# OBCv4_1.net
KiCad netlist of a schematic drawn in EAGLE
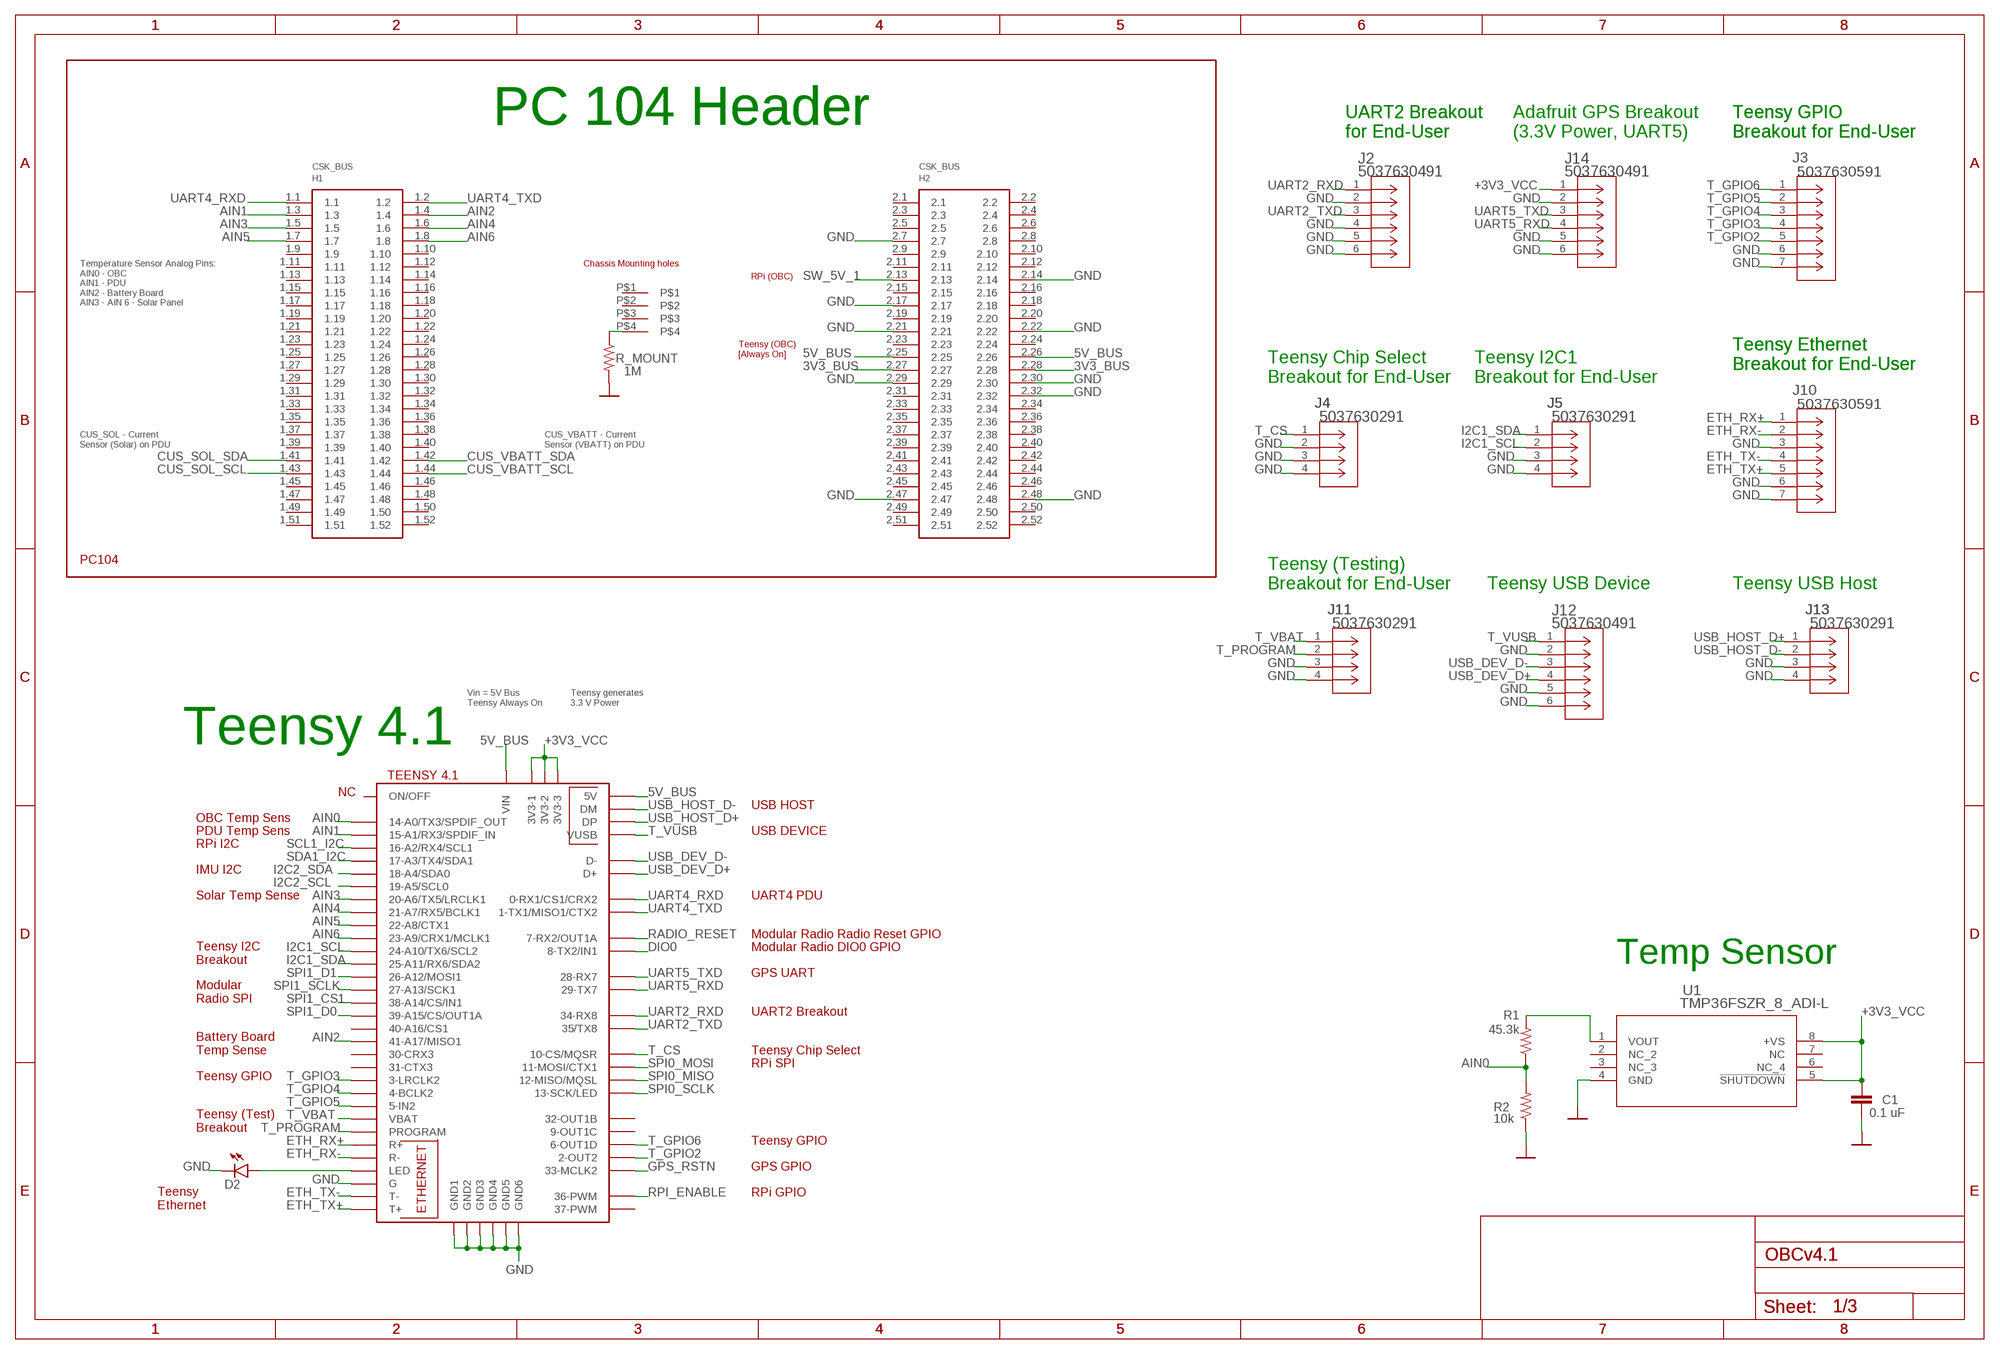
[diagram p0: schematic, sheet 1]
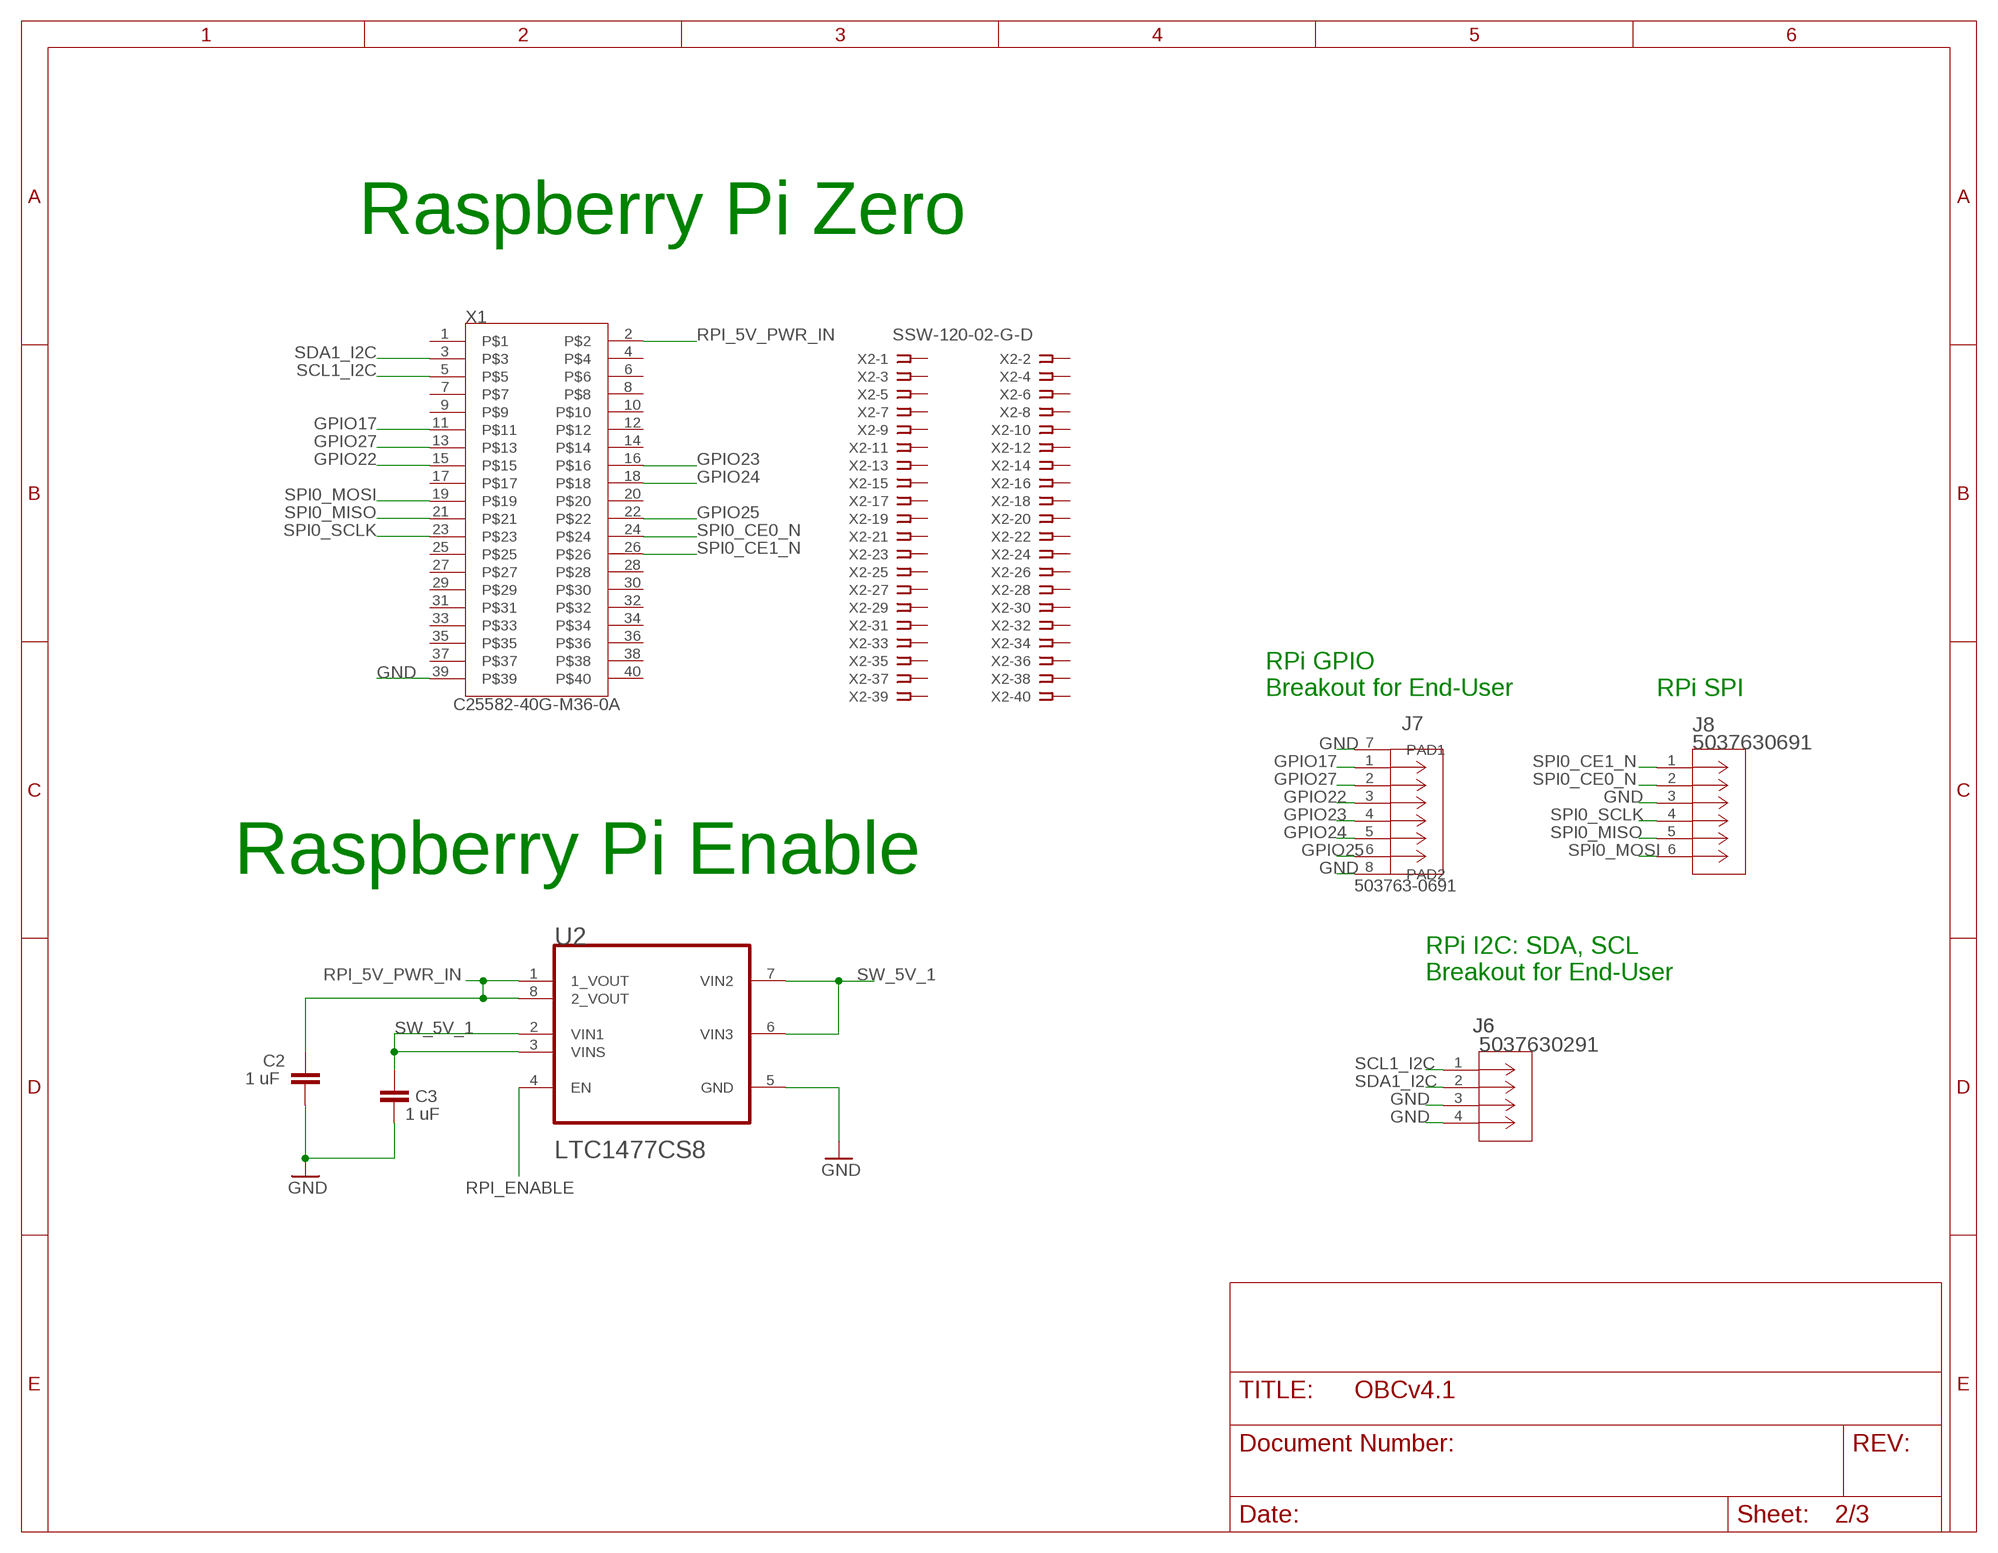
[diagram p1: schematic, sheet 2]
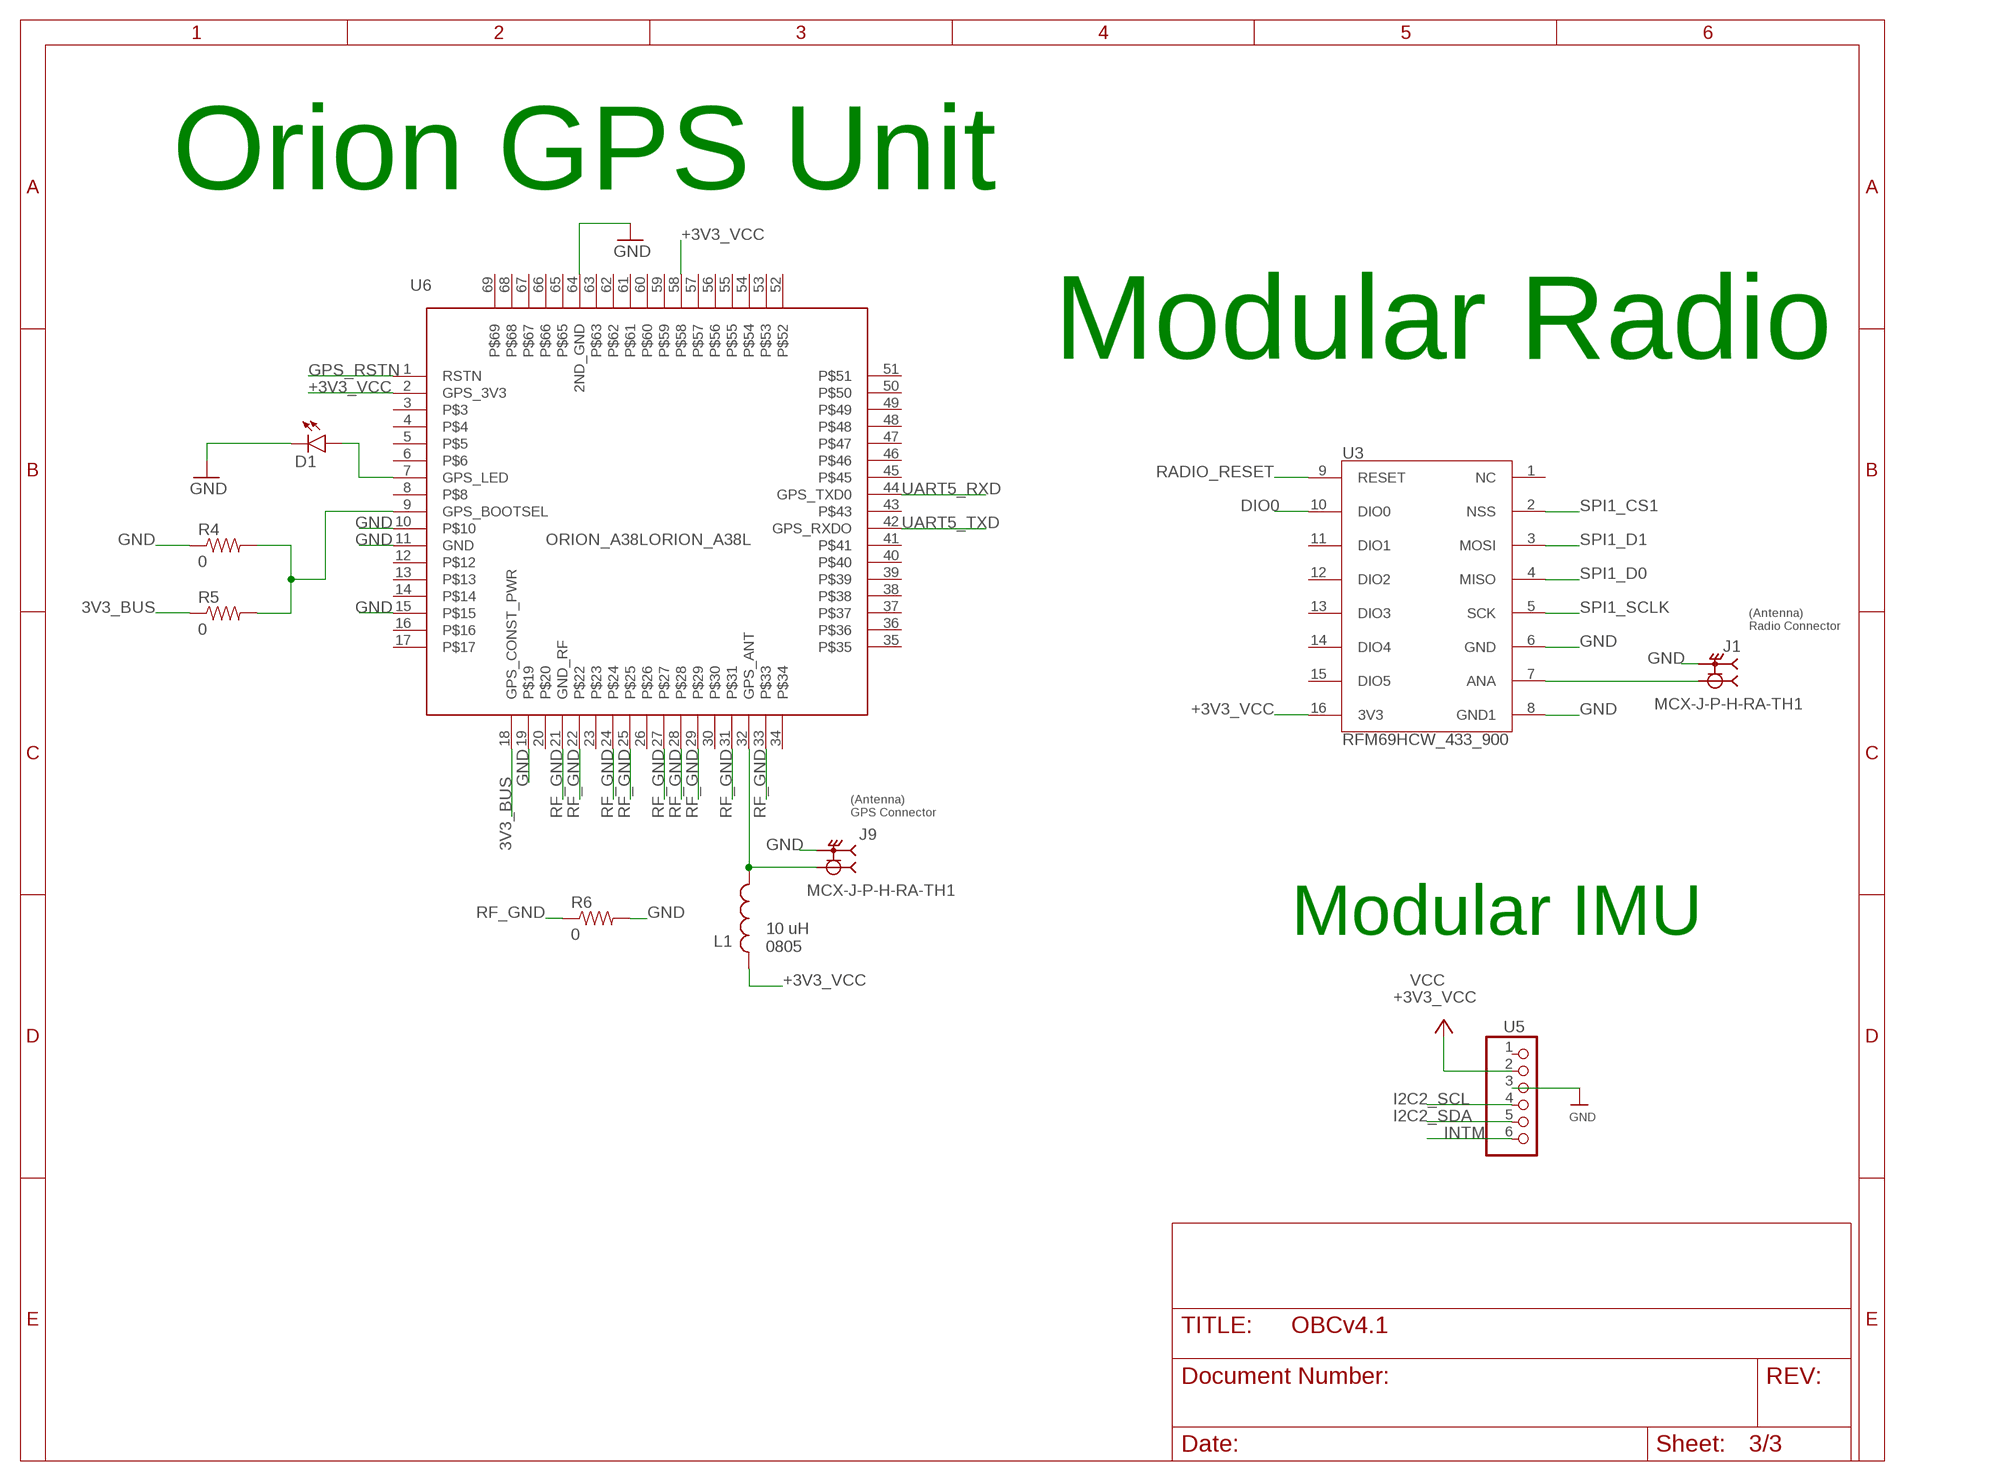
[diagram p2: schematic, sheet 3]

(export (version "E")
  (design (tool "Eeschema 10.0.6"))
  (components
    (comp (ref "C1")
      (value "0.1 uF")
      (footprint "eagle-import:0805")
      (libsource (lib "eagle-import") (part "CAP0805"))
    )
    (comp (ref "D2")
      (value "LEDCHIP-LED0603")
      (footprint "eagle-import:CHIP-LED0603")
      (libsource (lib "eagle-import") (part "LEDCHIP-LED0603"))
    )
    (comp (ref "H1")
      (value "PC104_WCONN")
      (footprint "eagle-import:PC104_WCONN")
      (libsource (lib "eagle-import") (part "PC104_WCONN"))
    )
    (comp (ref "J2")
      (value "5037630491")
      (footprint "eagle-import:CON_5037630491")
      (fields (field (name "COPYRIGHT") "Copyright (C) 2018 Accelerated Designs. All rights reserved"))
      (libsource (lib "eagle-import") (part "5037630491"))
    )
    (comp (ref "J3")
      (value "5037630591")
      (footprint "eagle-import:CON_5037630591")
      (fields (field (name "COPYRIGHT") "Copyright (C) 2021 Ultra Librarian. All rights reserved."))
      (libsource (lib "eagle-import") (part "5037630591"))
    )
    (comp (ref "J4")
      (value "5037630291")
      (footprint "eagle-import:CON_5037630291")
      (fields (field (name "COPYRIGHT") "Copyright (C) 2018 Accelerated Designs. All rights reserved"))
      (libsource (lib "eagle-import") (part "5037630291"))
    )
    (comp (ref "J5")
      (value "5037630291")
      (footprint "eagle-import:CON_5037630291")
      (fields (field (name "COPYRIGHT") "Copyright (C) 2018 Accelerated Designs. All rights reserved"))
      (libsource (lib "eagle-import") (part "5037630291"))
    )
    (comp (ref "J10")
      (value "5037630591")
      (footprint "eagle-import:CON_5037630591")
      (fields (field (name "COPYRIGHT") "Copyright (C) 2021 Ultra Librarian. All rights reserved."))
      (libsource (lib "eagle-import") (part "5037630591"))
    )
    (comp (ref "J11")
      (value "5037630291")
      (footprint "eagle-import:CON_5037630291")
      (fields (field (name "COPYRIGHT") "Copyright (C) 2018 Accelerated Designs. All rights reserved"))
      (libsource (lib "eagle-import") (part "5037630291"))
    )
    (comp (ref "J12")
      (value "5037630491")
      (footprint "eagle-import:CON_5037630491")
      (fields (field (name "COPYRIGHT") "Copyright (C) 2018 Accelerated Designs. All rights reserved"))
      (libsource (lib "eagle-import") (part "5037630491"))
    )
    (comp (ref "J13")
      (value "5037630291")
      (footprint "eagle-import:CON_5037630291")
      (fields (field (name "COPYRIGHT") "Copyright (C) 2018 Accelerated Designs. All rights reserved"))
      (libsource (lib "eagle-import") (part "5037630291"))
    )
    (comp (ref "J14")
      (value "5037630491")
      (footprint "eagle-import:CON_5037630491")
      (fields (field (name "COPYRIGHT") "Copyright (C) 2018 Accelerated Designs. All rights reserved"))
      (libsource (lib "eagle-import") (part "5037630491"))
    )
    (comp (ref "R1")
      (value "45.3k")
      (footprint "eagle-import:0805")
      (libsource (lib "eagle-import") (part "RESISTOR0805-RES"))
    )
    (comp (ref "R2")
      (value "10k")
      (footprint "eagle-import:0805")
      (libsource (lib "eagle-import") (part "RESISTOR0805-RES"))
    )
    (comp (ref "R_MOUNT")
      (value "1M")
      (footprint "eagle-import:0805")
      (libsource (lib "eagle-import") (part "RESISTOR0805-RES"))
    )
    (comp (ref "U$1")
      (value "TEENSY41")
      (footprint "eagle-import:TEENSY41")
      (libsource (lib "eagle-import") (part "TEENSY41"))
    )
    (comp (ref "U1")
      (value "TMP36FSZR_8_ADI-L")
      (footprint "eagle-import:R_8_ADI-L")
      (fields
        (field (name "MANUFACTURER_PART_NUMBER") "TMP36FSZ")
        (field (name "COPYRIGHT") "Copyright (C) 2021 Ultra Librarian. All rights reserved.")
      )
      (libsource (lib "eagle-import") (part "TMP36FSZR_8_ADI-L"))
    )
    (comp (ref "C2")
      (value "1 uF")
      (footprint "eagle-import:0805")
      (libsource (lib "eagle-import") (part "CAP0805"))
    )
    (comp (ref "C3")
      (value "1 uF")
      (footprint "eagle-import:0805")
      (libsource (lib "eagle-import") (part "CAP0805"))
    )
    (comp (ref "J6")
      (value "5037630291")
      (footprint "eagle-import:CON_5037630291")
      (fields (field (name "COPYRIGHT") "Copyright (C) 2018 Accelerated Designs. All rights reserved"))
      (libsource (lib "eagle-import") (part "5037630291"))
    )
    (comp (ref "J7")
      (value "503763-0691")
      (footprint "eagle-import:CONN_503763-0691_MOL")
      (fields (field (name "COPYRIGHT") "Copyright (C) 2018 Accelerated Designs. All rights reserved"))
      (libsource (lib "eagle-import") (part "503763-0691"))
    )
    (comp (ref "J8")
      (value "5037630691")
      (footprint "eagle-import:CONN_503763-0691_MOL")
      (fields
        (field (name "MANUFACTURER_PART_NUMBER") "503763-0691")
        (field (name "COPYRIGHT") "Copyright (C) 2018 Accelerated Designs. All rights reserved")
      )
      (libsource (lib "eagle-import") (part "5037630691"))
    )
    (comp (ref "U2")
      (value "LTC1477CS8LINEAR_TECHNOLOGY_LTC1477CS8_0_2")
      (footprint "eagle-import:LINEAR_TECHNOLOGY_LTC1477CS8_2")
      (fields (field (name "MF") "Linear Technology") (field (name "MPN") "LTC1477CS8"))
      (libsource (lib "eagle-import") (part "LTC1477CS8LINEAR_TECHNOLOGY_LTC1477CS8_0_2"))
    )
    (comp (ref "X1")
      (value "C25582-40G-M36-0A")
      (footprint "eagle-import:ADAFRUIT_C25582-40G-M36-0A_0")
      (libsource (lib "eagle-import") (part "C25582-40G-M36-0A"))
    )
    (comp (ref "X2")
      (value "SSW-120-02-G-D")
      (footprint "eagle-import:SSW-120-02-G-D")
      (fields (field (name "MF") "Samtec Inc."))
      (libsource (lib "eagle-import") (part "SSW-120-02-G-D"))
    )
    (comp (ref "D1")
      (value "LEDCHIP-LED0603")
      (footprint "eagle-import:CHIP-LED0603")
      (libsource (lib "eagle-import") (part "LEDCHIP-LED0603"))
    )
    (comp (ref "J1")
      (value "MCX-J-P-H-RA-TH1")
      (footprint "eagle-import:SAMTEC_MCX-J-P-H-RA-TH1")
      (fields (field (name "DIGI-KEY_PART_NUMBER") "SAM10607-ND") (field (name "MF") "Samtec"))
      (libsource (lib "eagle-import") (part "MCX-J-P-H-RA-TH1"))
    )
    (comp (ref "J9")
      (value "MCX-J-P-H-RA-TH1")
      (footprint "eagle-import:SAMTEC_MCX-J-P-H-RA-TH1")
      (fields (field (name "DIGI-KEY_PART_NUMBER") "SAM10607-ND") (field (name "MF") "Samtec"))
      (libsource (lib "eagle-import") (part "MCX-J-P-H-RA-TH1"))
    )
    (comp (ref "L1")
      (value "L")
      (footprint "eagle-import:INDC2012X145N")
      (fields
        (field (name "DIGI-KEY_PART_NUMBER") "490-18463-1-ND")
        (field (name "MF") "Murata Electronics North America")
        (field (name "MP") "LQM21DH100M70L")
      )
      (libsource (lib "eagle-import") (part "L"))
    )
    (comp (ref "R4")
      (value "0")
      (footprint "eagle-import:0805")
      (libsource (lib "eagle-import") (part "RESISTOR0805-RES"))
    )
    (comp (ref "R5")
      (value "0")
      (footprint "eagle-import:0805")
      (libsource (lib "eagle-import") (part "RESISTOR0805-RES"))
    )
    (comp (ref "R6")
      (value "0")
      (footprint "eagle-import:0805")
      (libsource (lib "eagle-import") (part "RESISTOR0805-RES"))
    )
    (comp (ref "U3")
      (value "RFM69HCW_433_900")
      (footprint "eagle-import:RFM69HCW_433")
      (libsource (lib "eagle-import") (part "RFM69HCW_433_900"))
    )
    (comp (ref "U5")
      (value "HEADER-1X670MIL")
      (footprint "eagle-import:1X06_ROUND_70")
      (libsource (lib "eagle-import") (part "HEADER-1X670MIL"))
    )
    (comp (ref "U6")
      (value "ORION_A38LORION_A38L")
      (footprint "eagle-import:ORION_A38L")
      (libsource (lib "eagle-import") (part "ORION_A38LORION_A38L"))
    )
  )
  (nets
    (net (code "1") (name "+3V3_VCC") (class "Default")
      (node (ref "C1") (pin "1") (pinfunction "1_1") (pintype "passive"))
      (node (ref "J14") (pin "1") (pinfunction "1_1") (pintype "passive"))
      (node (ref "L1") (pin "1") (pinfunction "1_1") (pintype "passive"))
      (node (ref "U$1") (pin "3V3-1") (pinfunction "3V3-1_3V3-1") (pintype "bidirectional"))
      (node (ref "U$1") (pin "3V3-2") (pinfunction "3V3-2_3V3-2") (pintype "bidirectional"))
      (node (ref "U$1") (pin "3V3-3") (pinfunction "3V3-3_3V3-3") (pintype "bidirectional"))
      (node (ref "U1") (pin "5") (pinfunction "~{SHUTDOWN}_5") (pintype "passive"))
      (node (ref "U1") (pin "8") (pinfunction "+VS_8") (pintype "power_in"))
      (node (ref "U3") (pin "16") (pinfunction "3V3_16") (pintype "bidirectional"))
      (node (ref "U5") (pin "2") (pinfunction "2_2") (pintype "passive"))
      (node (ref "U6") (pin "2") (pinfunction "GPS_3V3_2") (pintype "bidirectional"))
      (node (ref "U6") (pin "58") (pinfunction "P$58_58") (pintype "bidirectional"))
    )
    (net (code "2") (name "3V3_BUS") (class "Default")
      (node (ref "H1") (pin "2.27") (pinfunction "2.27_2.27") (pintype "bidirectional"))
      (node (ref "H1") (pin "2.28") (pinfunction "2.28_2.28") (pintype "bidirectional"))
      (node (ref "R5") (pin "1") (pinfunction "1_1") (pintype "passive"))
      (node (ref "U6") (pin "18") (pinfunction "GPS_CONST_PWR_18") (pintype "bidirectional"))
    )
    (net (code "3") (name "5V_BUS") (class "Default")
      (node (ref "H1") (pin "2.25") (pinfunction "2.25_2.25") (pintype "bidirectional"))
      (node (ref "H1") (pin "2.26") (pinfunction "2.26_2.26") (pintype "bidirectional"))
      (node (ref "U$1") (pin "+5V") (pinfunction "5V_+5V") (pintype "bidirectional"))
      (node (ref "U$1") (pin "VIN") (pinfunction "VIN_VIN") (pintype "bidirectional"))
    )
    (net (code "4") (name "AIN0") (class "Default")
      (node (ref "R1") (pin "1") (pinfunction "1_1") (pintype "passive"))
      (node (ref "R2") (pin "2") (pinfunction "2_2") (pintype "passive"))
      (node (ref "U$1") (pin "14-A0/TX3/SPDIF_OUT") (pinfunction "14-A0/TX3/SPDIF_OUT_14-A0/TX3/SPDIF_OUT") (pintype "bidirectional"))
    )
    (net (code "5") (name "AIN1") (class "Default")
      (node (ref "H1") (pin "1.3") (pinfunction "1.3_1.3") (pintype "bidirectional"))
      (node (ref "U$1") (pin "15-A1/RX3/SPDIF_IN") (pinfunction "15-A1/RX3/SPDIF_IN_15-A1/RX3/SPDIF_IN") (pintype "bidirectional"))
    )
    (net (code "6") (name "AIN2") (class "Default")
      (node (ref "H1") (pin "1.4") (pinfunction "1.4_1.4") (pintype "bidirectional"))
      (node (ref "U$1") (pin "41-A17/MISO1") (pinfunction "41-A17/MISO1_41-A17/MISO1") (pintype "bidirectional"))
    )
    (net (code "7") (name "AIN3") (class "Default")
      (node (ref "H1") (pin "1.5") (pinfunction "1.5_1.5") (pintype "bidirectional"))
      (node (ref "U$1") (pin "20-A6/TX5/LRCLK1") (pinfunction "20-A6/TX5/LRCLK1_20-A6/TX5/LRCLK1") (pintype "bidirectional"))
    )
    (net (code "8") (name "AIN4") (class "Default")
      (node (ref "H1") (pin "1.6") (pinfunction "1.6_1.6") (pintype "bidirectional"))
      (node (ref "U$1") (pin "21-A7/RX5/BCLK1") (pinfunction "21-A7/RX5/BCLK1_21-A7/RX5/BCLK1") (pintype "bidirectional"))
    )
    (net (code "9") (name "AIN5") (class "Default")
      (node (ref "H1") (pin "1.7") (pinfunction "1.7_1.7") (pintype "bidirectional"))
      (node (ref "U$1") (pin "22-A8/CTX1") (pinfunction "22-A8/CTX1_22-A8/CTX1") (pintype "bidirectional"))
    )
    (net (code "10") (name "AIN6") (class "Default")
      (node (ref "H1") (pin "1.8") (pinfunction "1.8_1.8") (pintype "bidirectional"))
      (node (ref "U$1") (pin "23-A9/CRX1/MCLK1") (pinfunction "23-A9/CRX1/MCLK1_23-A9/CRX1/MCLK1") (pintype "bidirectional"))
    )
    (net (code "11") (name "CUS_SOL_SCL") (class "Default")
      (node (ref "H1") (pin "1.43") (pinfunction "1.43_1.43") (pintype "bidirectional"))
    )
    (net (code "12") (name "CUS_SOL_SDA") (class "Default")
      (node (ref "H1") (pin "1.41") (pinfunction "1.41_1.41") (pintype "bidirectional"))
    )
    (net (code "13") (name "CUS_VBATT_SCL") (class "Default")
      (node (ref "H1") (pin "1.44") (pinfunction "1.44_1.44") (pintype "bidirectional"))
    )
    (net (code "14") (name "CUS_VBATT_SDA") (class "Default")
      (node (ref "H1") (pin "1.42") (pinfunction "1.42_1.42") (pintype "bidirectional"))
    )
    (net (code "15") (name "DIO0") (class "Default")
      (node (ref "U$1") (pin "8-TX2/IN1") (pinfunction "8-TX2/IN1_8-TX2/IN1") (pintype "bidirectional"))
      (node (ref "U3") (pin "10") (pinfunction "DIO0_10") (pintype "bidirectional"))
    )
    (net (code "16") (name "ETH_RX+") (class "Default")
      (node (ref "J10") (pin "1") (pinfunction "1_1") (pintype "passive"))
      (node (ref "U$1") (pin "R+") (pinfunction "R+_R+") (pintype "bidirectional"))
    )
    (net (code "17") (name "ETH_RX-") (class "Default")
      (node (ref "J10") (pin "2") (pinfunction "2_2") (pintype "passive"))
      (node (ref "U$1") (pin "R-") (pinfunction "R-_R-") (pintype "bidirectional"))
    )
    (net (code "18") (name "ETH_TX+") (class "Default")
      (node (ref "J10") (pin "5") (pinfunction "5_5") (pintype "passive"))
      (node (ref "U$1") (pin "T+") (pinfunction "T+_T+") (pintype "bidirectional"))
    )
    (net (code "19") (name "ETH_TX-") (class "Default")
      (node (ref "J10") (pin "4") (pinfunction "4_4") (pintype "passive"))
      (node (ref "U$1") (pin "T-") (pinfunction "T-_T-") (pintype "bidirectional"))
    )
    (net (code "20") (name "GND") (class "Default")
      (node (ref "C1") (pin "2") (pinfunction "2_2") (pintype "passive"))
      (node (ref "C2") (pin "2") (pinfunction "2_2") (pintype "passive"))
      (node (ref "C3") (pin "2") (pinfunction "2_2") (pintype "passive"))
      (node (ref "D1") (pin "C") (pinfunction "C_C") (pintype "passive"))
      (node (ref "D2") (pin "C") (pinfunction "C_C") (pintype "passive"))
      (node (ref "H1") (pin "2.14") (pinfunction "2.14_2.14") (pintype "bidirectional"))
      (node (ref "H1") (pin "2.17") (pinfunction "2.17_2.17") (pintype "bidirectional"))
      (node (ref "H1") (pin "2.21") (pinfunction "2.21_2.21") (pintype "bidirectional"))
      (node (ref "H1") (pin "2.22") (pinfunction "2.22_2.22") (pintype "bidirectional"))
      (node (ref "H1") (pin "2.29") (pinfunction "2.29_2.29") (pintype "bidirectional"))
      (node (ref "H1") (pin "2.30") (pinfunction "2.30_2.30") (pintype "bidirectional"))
      (node (ref "H1") (pin "2.32") (pinfunction "2.32_2.32") (pintype "bidirectional"))
      (node (ref "H1") (pin "2.47") (pinfunction "2.47_2.47") (pintype "bidirectional"))
      (node (ref "H1") (pin "2.48") (pinfunction "2.48_2.48") (pintype "bidirectional"))
      (node (ref "H1") (pin "2.7") (pinfunction "2.7_2.7") (pintype "bidirectional"))
      (node (ref "J1") (pin "S1") (pinfunction "2_S1") (pintype "passive"))
      (node (ref "J1") (pin "S2") (pinfunction "2_S2") (pintype "passive"))
      (node (ref "J1") (pin "S3") (pinfunction "2_S3") (pintype "passive"))
      (node (ref "J1") (pin "S4") (pinfunction "2_S4") (pintype "passive"))
      (node (ref "J10") (pin "3") (pinfunction "3_3") (pintype "passive"))
      (node (ref "J10") (pin "6") (pinfunction "6_6") (pintype "passive"))
      (node (ref "J10") (pin "7") (pinfunction "7_7") (pintype "passive"))
      (node (ref "J11") (pin "3") (pinfunction "3_3") (pintype "passive"))
      (node (ref "J11") (pin "4") (pinfunction "4_4") (pintype "passive"))
      (node (ref "J12") (pin "2") (pinfunction "2_2") (pintype "passive"))
      (node (ref "J12") (pin "5") (pinfunction "5_5") (pintype "passive"))
      (node (ref "J12") (pin "6") (pinfunction "6_6") (pintype "passive"))
      (node (ref "J13") (pin "3") (pinfunction "3_3") (pintype "passive"))
      (node (ref "J13") (pin "4") (pinfunction "4_4") (pintype "passive"))
      (node (ref "J14") (pin "2") (pinfunction "2_2") (pintype "passive"))
      (node (ref "J14") (pin "5") (pinfunction "5_5") (pintype "passive"))
      (node (ref "J14") (pin "6") (pinfunction "6_6") (pintype "passive"))
      (node (ref "J2") (pin "2") (pinfunction "2_2") (pintype "passive"))
      (node (ref "J2") (pin "4") (pinfunction "4_4") (pintype "passive"))
      (node (ref "J2") (pin "5") (pinfunction "5_5") (pintype "passive"))
      (node (ref "J2") (pin "6") (pinfunction "6_6") (pintype "passive"))
      (node (ref "J3") (pin "6") (pinfunction "6_6") (pintype "passive"))
      (node (ref "J3") (pin "7") (pinfunction "7_7") (pintype "passive"))
      (node (ref "J4") (pin "2") (pinfunction "2_2") (pintype "passive"))
      (node (ref "J4") (pin "3") (pinfunction "3_3") (pintype "passive"))
      (node (ref "J4") (pin "4") (pinfunction "4_4") (pintype "passive"))
      (node (ref "J5") (pin "3") (pinfunction "3_3") (pintype "passive"))
      (node (ref "J5") (pin "4") (pinfunction "4_4") (pintype "passive"))
      (node (ref "J6") (pin "3") (pinfunction "3_3") (pintype "passive"))
      (node (ref "J6") (pin "4") (pinfunction "4_4") (pintype "passive"))
      (node (ref "J7") (pin "7") (pinfunction "PAD1_7") (pintype "bidirectional"))
      (node (ref "J7") (pin "8") (pinfunction "PAD2_8") (pintype "bidirectional"))
      (node (ref "J8") (pin "3") (pinfunction "3_3") (pintype "passive"))
      (node (ref "J9") (pin "S1") (pinfunction "2_S1") (pintype "passive"))
      (node (ref "J9") (pin "S2") (pinfunction "2_S2") (pintype "passive"))
      (node (ref "J9") (pin "S3") (pinfunction "2_S3") (pintype "passive"))
      (node (ref "J9") (pin "S4") (pinfunction "2_S4") (pintype "passive"))
      (node (ref "R2") (pin "1") (pinfunction "1_1") (pintype "passive"))
      (node (ref "R4") (pin "1") (pinfunction "1_1") (pintype "passive"))
      (node (ref "R6") (pin "2") (pinfunction "2_2") (pintype "passive"))
      (node (ref "R_MOUNT") (pin "2") (pinfunction "2_2") (pintype "passive"))
      (node (ref "U$1") (pin "G") (pinfunction "G_G") (pintype "bidirectional"))
      (node (ref "U$1") (pin "GND1") (pinfunction "GND1_GND1") (pintype "bidirectional"))
      (node (ref "U$1") (pin "GND2") (pinfunction "GND2_GND2") (pintype "bidirectional"))
      (node (ref "U$1") (pin "GND3") (pinfunction "GND3_GND3") (pintype "bidirectional"))
      (node (ref "U$1") (pin "GND4") (pinfunction "GND4_GND4") (pintype "bidirectional"))
      (node (ref "U$1") (pin "GND5") (pinfunction "GND5_GND5") (pintype "bidirectional"))
      (node (ref "U$1") (pin "GND6") (pinfunction "GND6_GND6") (pintype "bidirectional"))
      (node (ref "U1") (pin "4") (pinfunction "GND_4") (pintype "passive"))
      (node (ref "U2") (pin "5") (pinfunction "GND_5") (pintype "power_in"))
      (node (ref "U3") (pin "6") (pinfunction "GND_6") (pintype "bidirectional"))
      (node (ref "U3") (pin "8") (pinfunction "GND1_8") (pintype "bidirectional"))
      (node (ref "U5") (pin "3") (pinfunction "3_3") (pintype "passive"))
      (node (ref "U6") (pin "10") (pinfunction "P$10_10") (pintype "bidirectional"))
      (node (ref "U6") (pin "11") (pinfunction "GND_11") (pintype "bidirectional"))
      (node (ref "U6") (pin "15") (pinfunction "P$15_15") (pintype "bidirectional"))
      (node (ref "U6") (pin "19") (pinfunction "P$19_19") (pintype "bidirectional"))
      (node (ref "U6") (pin "64") (pinfunction "2ND_GND_64") (pintype "bidirectional"))
      (node (ref "X1") (pin "39") (pinfunction "P$39_39") (pintype "bidirectional"))
    )
    (net (code "21") (name "GPIO17") (class "Default")
      (node (ref "J7") (pin "1") (pinfunction "1_1") (pintype "passive"))
      (node (ref "X1") (pin "11") (pinfunction "P$11_11") (pintype "bidirectional"))
    )
    (net (code "22") (name "GPIO22") (class "Default")
      (node (ref "J7") (pin "3") (pinfunction "3_3") (pintype "passive"))
      (node (ref "X1") (pin "15") (pinfunction "P$15_15") (pintype "bidirectional"))
    )
    (net (code "23") (name "GPIO23") (class "Default")
      (node (ref "J7") (pin "4") (pinfunction "4_4") (pintype "passive"))
      (node (ref "X1") (pin "16") (pinfunction "P$16_16") (pintype "bidirectional"))
    )
    (net (code "24") (name "GPIO24") (class "Default")
      (node (ref "J7") (pin "5") (pinfunction "5_5") (pintype "passive"))
      (node (ref "X1") (pin "18") (pinfunction "P$18_18") (pintype "bidirectional"))
    )
    (net (code "25") (name "GPIO25") (class "Default")
      (node (ref "J7") (pin "6") (pinfunction "6_6") (pintype "passive"))
      (node (ref "X1") (pin "22") (pinfunction "P$22_22") (pintype "bidirectional"))
    )
    (net (code "26") (name "GPIO27") (class "Default")
      (node (ref "J7") (pin "2") (pinfunction "2_2") (pintype "passive"))
      (node (ref "X1") (pin "13") (pinfunction "P$13_13") (pintype "bidirectional"))
    )
    (net (code "27") (name "GPS_RSTN") (class "Default")
      (node (ref "U$1") (pin "33-MCLK2") (pinfunction "33-MCLK2_33-MCLK2") (pintype "bidirectional"))
      (node (ref "U6") (pin "1") (pinfunction "RSTN_1") (pintype "bidirectional"))
    )
    (net (code "28") (name "I2C1_SCL") (class "Default")
      (node (ref "J5") (pin "2") (pinfunction "2_2") (pintype "passive"))
      (node (ref "U$1") (pin "24-A10/TX6/SCL2") (pinfunction "24-A10/TX6/SCL2_24-A10/TX6/SCL2") (pintype "bidirectional"))
    )
    (net (code "29") (name "I2C1_SDA") (class "Default")
      (node (ref "J5") (pin "1") (pinfunction "1_1") (pintype "passive"))
      (node (ref "U$1") (pin "25-A11/RX6/SDA2") (pinfunction "25-A11/RX6/SDA2_25-A11/RX6/SDA2") (pintype "bidirectional"))
    )
    (net (code "30") (name "I2C2_SCL") (class "Default")
      (node (ref "U$1") (pin "19-A5/SCL0") (pinfunction "19-A5/SCL0_19-A5/SCL0") (pintype "bidirectional"))
      (node (ref "U5") (pin "4") (pinfunction "4_4") (pintype "passive"))
    )
    (net (code "31") (name "I2C2_SDA") (class "Default")
      (node (ref "U$1") (pin "18-A4/SDA0") (pinfunction "18-A4/SDA0_18-A4/SDA0") (pintype "bidirectional"))
      (node (ref "U5") (pin "5") (pinfunction "5_5") (pintype "passive"))
    )
    (net (code "32") (name "INTM") (class "Default")
      (node (ref "U5") (pin "6") (pinfunction "6_6") (pintype "passive"))
    )
    (net (code "33") (name "Net-(D2-PadA)") (class "Default")
      (node (ref "D2") (pin "A") (pinfunction "A_A") (pintype "passive"))
      (node (ref "U$1") (pin "LED") (pinfunction "LED_LED") (pintype "bidirectional"))
    )
    (net (code "34") (name "Net-(H1-PadP$4)") (class "Default")
      (node (ref "H1") (pin "P$4") (pinfunction "P$4_P$4") (pintype "bidirectional"))
      (node (ref "R_MOUNT") (pin "1") (pinfunction "1_1") (pintype "passive"))
    )
    (net (code "35") (name "Net-(U1-VOUT)") (class "Default")
      (node (ref "R1") (pin "2") (pinfunction "2_2") (pintype "passive"))
      (node (ref "U1") (pin "1") (pinfunction "VOUT_1") (pintype "output"))
    )
    (net (code "36") (name "Net-(U3-ANA)") (class "Default")
      (node (ref "J1") (pin "1") (pinfunction "1_1") (pintype "passive"))
      (node (ref "U3") (pin "7") (pinfunction "ANA_7") (pintype "bidirectional"))
    )
    (net (code "37") (name "Net-(U6-GPS_ANT)") (class "Default")
      (node (ref "J9") (pin "1") (pinfunction "1_1") (pintype "passive"))
      (node (ref "L1") (pin "2") (pinfunction "2_2") (pintype "passive"))
      (node (ref "U6") (pin "32") (pinfunction "GPS_ANT_32") (pintype "bidirectional"))
    )
    (net (code "38") (name "Net-(U6-GPS_BOOTSEL)") (class "Default")
      (node (ref "R4") (pin "2") (pinfunction "2_2") (pintype "passive"))
      (node (ref "R5") (pin "2") (pinfunction "2_2") (pintype "passive"))
      (node (ref "U6") (pin "9") (pinfunction "GPS_BOOTSEL_9") (pintype "bidirectional"))
    )
    (net (code "39") (name "Net-(U6-GPS_LED)") (class "Default")
      (node (ref "D1") (pin "A") (pinfunction "A_A") (pintype "passive"))
      (node (ref "U6") (pin "7") (pinfunction "GPS_LED_7") (pintype "bidirectional"))
    )
    (net (code "40") (name "RADIO_RESET") (class "Default")
      (node (ref "U$1") (pin "7-RX2/OUT1A") (pinfunction "7-RX2/OUT1A_7-RX2/OUT1A") (pintype "bidirectional"))
      (node (ref "U3") (pin "9") (pinfunction "RESET_9") (pintype "bidirectional"))
    )
    (net (code "41") (name "RF_GND") (class "Default")
      (node (ref "R6") (pin "1") (pinfunction "1_1") (pintype "passive"))
      (node (ref "U6") (pin "21") (pinfunction "GND_RF_21") (pintype "bidirectional"))
      (node (ref "U6") (pin "22") (pinfunction "P$22_22") (pintype "bidirectional"))
      (node (ref "U6") (pin "24") (pinfunction "P$24_24") (pintype "bidirectional"))
      (node (ref "U6") (pin "25") (pinfunction "P$25_25") (pintype "bidirectional"))
      (node (ref "U6") (pin "27") (pinfunction "P$27_27") (pintype "bidirectional"))
      (node (ref "U6") (pin "28") (pinfunction "P$28_28") (pintype "bidirectional"))
      (node (ref "U6") (pin "29") (pinfunction "P$29_29") (pintype "bidirectional"))
      (node (ref "U6") (pin "31") (pinfunction "P$31_31") (pintype "bidirectional"))
      (node (ref "U6") (pin "33") (pinfunction "P$33_33") (pintype "bidirectional"))
    )
    (net (code "42") (name "RPI_5V_PWR_IN") (class "Default")
      (node (ref "C2") (pin "1") (pinfunction "1_1") (pintype "passive"))
      (node (ref "U2") (pin "1") (pinfunction "1_VOUT_1") (pintype "power_in"))
      (node (ref "U2") (pin "8") (pinfunction "2_VOUT_8") (pintype "power_in"))
      (node (ref "X1") (pin "2") (pinfunction "P$2_2") (pintype "bidirectional"))
    )
    (net (code "43") (name "RPI_ENABLE") (class "Default")
      (node (ref "U$1") (pin "36-PWM") (pinfunction "36-PWM_36-PWM") (pintype "bidirectional"))
      (node (ref "U2") (pin "4") (pinfunction "EN_4") (pintype "input"))
    )
    (net (code "44") (name "SCL1_I2C") (class "Default")
      (node (ref "J6") (pin "1") (pinfunction "1_1") (pintype "passive"))
      (node (ref "U$1") (pin "16-A2/RX4/SCL1") (pinfunction "16-A2/RX4/SCL1_16-A2/RX4/SCL1") (pintype "bidirectional"))
      (node (ref "X1") (pin "5") (pinfunction "P$5_5") (pintype "bidirectional"))
    )
    (net (code "45") (name "SDA1_I2C") (class "Default")
      (node (ref "J6") (pin "2") (pinfunction "2_2") (pintype "passive"))
      (node (ref "U$1") (pin "17-A3/TX4/SDA1") (pinfunction "17-A3/TX4/SDA1_17-A3/TX4/SDA1") (pintype "bidirectional"))
      (node (ref "X1") (pin "3") (pinfunction "P$3_3") (pintype "bidirectional"))
    )
    (net (code "46") (name "SPI0_CE0_N") (class "Default")
      (node (ref "J8") (pin "2") (pinfunction "2_2") (pintype "passive"))
      (node (ref "X1") (pin "24") (pinfunction "P$24_24") (pintype "bidirectional"))
    )
    (net (code "47") (name "SPI0_CE1_N") (class "Default")
      (node (ref "J8") (pin "1") (pinfunction "1_1") (pintype "passive"))
      (node (ref "X1") (pin "26") (pinfunction "P$26_26") (pintype "bidirectional"))
    )
    (net (code "48") (name "SPI0_MISO") (class "Default")
      (node (ref "J8") (pin "5") (pinfunction "5_5") (pintype "passive"))
      (node (ref "U$1") (pin "12-MISO/MQSL") (pinfunction "12-MISO/MQSL_12-MISO/MQSL") (pintype "bidirectional"))
      (node (ref "X1") (pin "21") (pinfunction "P$21_21") (pintype "bidirectional"))
    )
    (net (code "49") (name "SPI0_MOSI") (class "Default")
      (node (ref "J8") (pin "6") (pinfunction "6_6") (pintype "passive"))
      (node (ref "U$1") (pin "11-MOSI/CTX1") (pinfunction "11-MOSI/CTX1_11-MOSI/CTX1") (pintype "bidirectional"))
      (node (ref "X1") (pin "19") (pinfunction "P$19_19") (pintype "bidirectional"))
    )
    (net (code "50") (name "SPI0_SCLK") (class "Default")
      (node (ref "J8") (pin "4") (pinfunction "4_4") (pintype "passive"))
      (node (ref "U$1") (pin "13-SCK/LED") (pinfunction "13-SCK/LED_13-SCK/LED") (pintype "bidirectional"))
      (node (ref "X1") (pin "23") (pinfunction "P$23_23") (pintype "bidirectional"))
    )
    (net (code "51") (name "SPI1_CS1") (class "Default")
      (node (ref "U$1") (pin "38-A14/CS/IN1") (pinfunction "38-A14/CS/IN1_38-A14/CS/IN1") (pintype "bidirectional"))
      (node (ref "U3") (pin "2") (pinfunction "NSS_2") (pintype "bidirectional"))
    )
    (net (code "52") (name "SPI1_D0") (class "Default")
      (node (ref "U$1") (pin "39-A15/CS/OUT1A") (pinfunction "39-A15/CS/OUT1A_39-A15/CS/OUT1A") (pintype "bidirectional"))
      (node (ref "U3") (pin "4") (pinfunction "MISO_4") (pintype "bidirectional"))
    )
    (net (code "53") (name "SPI1_D1") (class "Default")
      (node (ref "U$1") (pin "26-A12/MOSI1") (pinfunction "26-A12/MOSI1_26-A12/MOSI1") (pintype "bidirectional"))
      (node (ref "U3") (pin "3") (pinfunction "MOSI_3") (pintype "bidirectional"))
    )
    (net (code "54") (name "SPI1_SCLK") (class "Default")
      (node (ref "U$1") (pin "27-A13/SCK1") (pinfunction "27-A13/SCK1_27-A13/SCK1") (pintype "bidirectional"))
      (node (ref "U3") (pin "5") (pinfunction "SCK_5") (pintype "bidirectional"))
    )
    (net (code "55") (name "SW_5V_1") (class "Default")
      (node (ref "C3") (pin "1") (pinfunction "1_1") (pintype "passive"))
      (node (ref "H1") (pin "2.13") (pinfunction "2.13_2.13") (pintype "bidirectional"))
      (node (ref "U2") (pin "2") (pinfunction "VIN1_2") (pintype "power_in"))
      (node (ref "U2") (pin "3") (pinfunction "VINS_3") (pintype "power_in"))
      (node (ref "U2") (pin "6") (pinfunction "VIN3_6") (pintype "power_in"))
      (node (ref "U2") (pin "7") (pinfunction "VIN2_7") (pintype "power_in"))
    )
    (net (code "56") (name "T_CS") (class "Default")
      (node (ref "J4") (pin "1") (pinfunction "1_1") (pintype "passive"))
      (node (ref "U$1") (pin "10-CS\\MQSR") (pinfunction "10-CS/MQSR_10-CS\\MQSR") (pintype "bidirectional"))
    )
    (net (code "57") (name "T_GPIO2") (class "Default")
      (node (ref "J3") (pin "5") (pinfunction "5_5") (pintype "passive"))
      (node (ref "U$1") (pin "2-OUT2") (pinfunction "2-OUT2_2-OUT2") (pintype "bidirectional"))
    )
    (net (code "58") (name "T_GPIO3") (class "Default")
      (node (ref "J3") (pin "4") (pinfunction "4_4") (pintype "passive"))
      (node (ref "U$1") (pin "3-LRCLK2") (pinfunction "3-LRCLK2_3-LRCLK2") (pintype "bidirectional"))
    )
    (net (code "59") (name "T_GPIO4") (class "Default")
      (node (ref "J3") (pin "3") (pinfunction "3_3") (pintype "passive"))
      (node (ref "U$1") (pin "4-BCLK2") (pinfunction "4-BCLK2_4-BCLK2") (pintype "bidirectional"))
    )
    (net (code "60") (name "T_GPIO5") (class "Default")
      (node (ref "J3") (pin "2") (pinfunction "2_2") (pintype "passive"))
      (node (ref "U$1") (pin "5-IN2") (pinfunction "5-IN2_5-IN2") (pintype "bidirectional"))
    )
    (net (code "61") (name "T_GPIO6") (class "Default")
      (node (ref "J3") (pin "1") (pinfunction "1_1") (pintype "passive"))
      (node (ref "U$1") (pin "6-OUT1D") (pinfunction "6-OUT1D_6-OUT1D") (pintype "bidirectional"))
    )
    (net (code "62") (name "T_PROGRAM") (class "Default")
      (node (ref "J11") (pin "2") (pinfunction "2_2") (pintype "passive"))
      (node (ref "U$1") (pin "PROGRAM") (pinfunction "PROGRAM_PROGRAM") (pintype "bidirectional"))
    )
    (net (code "63") (name "T_VBAT") (class "Default")
      (node (ref "J11") (pin "1") (pinfunction "1_1") (pintype "passive"))
      (node (ref "U$1") (pin "VBAT") (pinfunction "VBAT_VBAT") (pintype "bidirectional"))
    )
    (net (code "64") (name "T_VUSB") (class "Default")
      (node (ref "J12") (pin "1") (pinfunction "1_1") (pintype "passive"))
      (node (ref "U$1") (pin "VUSB") (pinfunction "VUSB_VUSB") (pintype "bidirectional"))
    )
    (net (code "65") (name "UART2_RXD") (class "Default")
      (node (ref "J2") (pin "1") (pinfunction "1_1") (pintype "passive"))
      (node (ref "U$1") (pin "34-RX8") (pinfunction "34-RX8_34-RX8") (pintype "bidirectional"))
    )
    (net (code "66") (name "UART2_TXD") (class "Default")
      (node (ref "J2") (pin "3") (pinfunction "3_3") (pintype "passive"))
      (node (ref "U$1") (pin "35-TX8") (pinfunction "35/TX8_35-TX8") (pintype "bidirectional"))
    )
    (net (code "67") (name "UART4_RXD") (class "Default")
      (node (ref "H1") (pin "1.1") (pinfunction "1.1_1.1") (pintype "bidirectional"))
      (node (ref "U$1") (pin "0-RX1/CS1/CRX2") (pinfunction "0-RX1/CS1/CRX2_0-RX1/CS1/CRX2") (pintype "bidirectional"))
    )
    (net (code "68") (name "UART4_TXD") (class "Default")
      (node (ref "H1") (pin "1.2") (pinfunction "1.2_1.2") (pintype "bidirectional"))
      (node (ref "U$1") (pin "1-TX1/MISO1/CTX2") (pinfunction "1-TX1/MISO1/CTX2_1-TX1/MISO1/CTX2") (pintype "bidirectional"))
    )
    (net (code "69") (name "UART5_RXD") (class "Default")
      (node (ref "J14") (pin "4") (pinfunction "4_4") (pintype "passive"))
      (node (ref "U$1") (pin "29-TX7") (pinfunction "29-TX7_29-TX7") (pintype "bidirectional"))
      (node (ref "U6") (pin "44") (pinfunction "GPS_TXD0_44") (pintype "output"))
    )
    (net (code "70") (name "UART5_TXD") (class "Default")
      (node (ref "J14") (pin "3") (pinfunction "3_3") (pintype "passive"))
      (node (ref "U$1") (pin "28-RX7") (pinfunction "28-RX7_28-RX7") (pintype "bidirectional"))
      (node (ref "U6") (pin "42") (pinfunction "GPS_RXDO_42") (pintype "input"))
    )
    (net (code "71") (name "USB_DEV_D+") (class "Default")
      (node (ref "J12") (pin "4") (pinfunction "4_4") (pintype "passive"))
      (node (ref "U$1") (pin "D+") (pinfunction "D+_D+") (pintype "bidirectional"))
    )
    (net (code "72") (name "USB_DEV_D-") (class "Default")
      (node (ref "J12") (pin "3") (pinfunction "3_3") (pintype "passive"))
      (node (ref "U$1") (pin "D-") (pinfunction "D-_D-") (pintype "bidirectional"))
    )
    (net (code "73") (name "USB_HOST_D+") (class "Default")
      (node (ref "J13") (pin "1") (pinfunction "1_1") (pintype "passive"))
      (node (ref "U$1") (pin "DP") (pinfunction "DP_DP") (pintype "bidirectional"))
    )
    (net (code "74") (name "USB_HOST_D-") (class "Default")
      (node (ref "J13") (pin "2") (pinfunction "2_2") (pintype "passive"))
      (node (ref "U$1") (pin "DM") (pinfunction "DM_DM") (pintype "bidirectional"))
    )
    (net (code "75") (name "unconnected-(H1-Pad1.9)") (class "Default")
      (node (ref "H1") (pin "1.9") (pinfunction "1.9_1.9") (pintype "bidirectional"))
    )
    (net (code "76") (name "unconnected-(H1-Pad1.10)") (class "Default")
      (node (ref "H1") (pin "1.10") (pinfunction "1.10_1.10") (pintype "bidirectional"))
    )
    (net (code "77") (name "unconnected-(H1-Pad1.11)") (class "Default")
      (node (ref "H1") (pin "1.11") (pinfunction "1.11_1.11") (pintype "bidirectional"))
    )
    (net (code "78") (name "unconnected-(H1-Pad1.12)") (class "Default")
      (node (ref "H1") (pin "1.12") (pinfunction "1.12_1.12") (pintype "bidirectional"))
    )
    (net (code "79") (name "unconnected-(H1-Pad1.13)") (class "Default")
      (node (ref "H1") (pin "1.13") (pinfunction "1.13_1.13") (pintype "bidirectional"))
    )
    (net (code "80") (name "unconnected-(H1-Pad1.14)") (class "Default")
      (node (ref "H1") (pin "1.14") (pinfunction "1.14_1.14") (pintype "bidirectional"))
    )
    (net (code "81") (name "unconnected-(H1-Pad1.15)") (class "Default")
      (node (ref "H1") (pin "1.15") (pinfunction "1.15_1.15") (pintype "bidirectional"))
    )
    (net (code "82") (name "unconnected-(H1-Pad1.16)") (class "Default")
      (node (ref "H1") (pin "1.16") (pinfunction "1.16_1.16") (pintype "bidirectional"))
    )
    (net (code "83") (name "unconnected-(H1-Pad1.17)") (class "Default")
      (node (ref "H1") (pin "1.17") (pinfunction "1.17_1.17") (pintype "bidirectional"))
    )
    (net (code "84") (name "unconnected-(H1-Pad1.18)") (class "Default")
      (node (ref "H1") (pin "1.18") (pinfunction "1.18_1.18") (pintype "bidirectional"))
    )
    (net (code "85") (name "unconnected-(H1-Pad1.19)") (class "Default")
      (node (ref "H1") (pin "1.19") (pinfunction "1.19_1.19") (pintype "bidirectional"))
    )
    (net (code "86") (name "unconnected-(H1-Pad1.20)") (class "Default")
      (node (ref "H1") (pin "1.20") (pinfunction "1.20_1.20") (pintype "bidirectional"))
    )
    (net (code "87") (name "unconnected-(H1-Pad1.21)") (class "Default")
      (node (ref "H1") (pin "1.21") (pinfunction "1.21_1.21") (pintype "bidirectional"))
    )
    (net (code "88") (name "unconnected-(H1-Pad1.22)") (class "Default")
      (node (ref "H1") (pin "1.22") (pinfunction "1.22_1.22") (pintype "bidirectional"))
    )
    (net (code "89") (name "unconnected-(H1-Pad1.23)") (class "Default")
      (node (ref "H1") (pin "1.23") (pinfunction "1.23_1.23") (pintype "bidirectional"))
    )
    (net (code "90") (name "unconnected-(H1-Pad1.24)") (class "Default")
      (node (ref "H1") (pin "1.24") (pinfunction "1.24_1.24") (pintype "bidirectional"))
    )
    (net (code "91") (name "unconnected-(H1-Pad1.25)") (class "Default")
      (node (ref "H1") (pin "1.25") (pinfunction "1.25_1.25") (pintype "bidirectional"))
    )
    (net (code "92") (name "unconnected-(H1-Pad1.26)") (class "Default")
      (node (ref "H1") (pin "1.26") (pinfunction "1.26_1.26") (pintype "bidirectional"))
    )
    (net (code "93") (name "unconnected-(H1-Pad1.27)") (class "Default")
      (node (ref "H1") (pin "1.27") (pinfunction "1.27_1.27") (pintype "bidirectional"))
    )
    (net (code "94") (name "unconnected-(H1-Pad1.28)") (class "Default")
      (node (ref "H1") (pin "1.28") (pinfunction "1.28_1.28") (pintype "bidirectional"))
    )
    (net (code "95") (name "unconnected-(H1-Pad1.29)") (class "Default")
      (node (ref "H1") (pin "1.29") (pinfunction "1.29_1.29") (pintype "bidirectional"))
    )
    (net (code "96") (name "unconnected-(H1-Pad1.30)") (class "Default")
      (node (ref "H1") (pin "1.30") (pinfunction "1.30_1.30") (pintype "bidirectional"))
    )
    (net (code "97") (name "unconnected-(H1-Pad1.31)") (class "Default")
      (node (ref "H1") (pin "1.31") (pinfunction "1.31_1.31") (pintype "bidirectional"))
    )
    (net (code "98") (name "unconnected-(H1-Pad1.32)") (class "Default")
      (node (ref "H1") (pin "1.32") (pinfunction "1.32_1.32") (pintype "bidirectional"))
    )
    (net (code "99") (name "unconnected-(H1-Pad1.33)") (class "Default")
      (node (ref "H1") (pin "1.33") (pinfunction "1.33_1.33") (pintype "bidirectional"))
    )
    (net (code "100") (name "unconnected-(H1-Pad1.34)") (class "Default")
      (node (ref "H1") (pin "1.34") (pinfunction "1.34_1.34") (pintype "bidirectional"))
    )
    (net (code "101") (name "unconnected-(H1-Pad1.35)") (class "Default")
      (node (ref "H1") (pin "1.35") (pinfunction "1.35_1.35") (pintype "bidirectional"))
    )
    (net (code "102") (name "unconnected-(H1-Pad1.36)") (class "Default")
      (node (ref "H1") (pin "1.36") (pinfunction "1.36_1.36") (pintype "bidirectional"))
    )
    (net (code "103") (name "unconnected-(H1-Pad1.37)") (class "Default")
      (node (ref "H1") (pin "1.37") (pinfunction "1.37_1.37") (pintype "bidirectional"))
    )
    (net (code "104") (name "unconnected-(H1-Pad1.38)") (class "Default")
      (node (ref "H1") (pin "1.38") (pinfunction "1.38_1.38") (pintype "bidirectional"))
    )
    (net (code "105") (name "unconnected-(H1-Pad1.39)") (class "Default")
      (node (ref "H1") (pin "1.39") (pinfunction "1.39_1.39") (pintype "bidirectional"))
    )
    (net (code "106") (name "unconnected-(H1-Pad1.40)") (class "Default")
      (node (ref "H1") (pin "1.40") (pinfunction "1.40_1.40") (pintype "bidirectional"))
    )
    (net (code "107") (name "unconnected-(H1-Pad1.45)") (class "Default")
      (node (ref "H1") (pin "1.45") (pinfunction "1.45_1.45") (pintype "bidirectional"))
    )
    (net (code "108") (name "unconnected-(H1-Pad1.46)") (class "Default")
      (node (ref "H1") (pin "1.46") (pinfunction "1.46_1.46") (pintype "bidirectional"))
    )
    (net (code "109") (name "unconnected-(H1-Pad1.47)") (class "Default")
      (node (ref "H1") (pin "1.47") (pinfunction "1.47_1.47") (pintype "bidirectional"))
    )
    (net (code "110") (name "unconnected-(H1-Pad1.48)") (class "Default")
      (node (ref "H1") (pin "1.48") (pinfunction "1.48_1.48") (pintype "bidirectional"))
    )
    (net (code "111") (name "unconnected-(H1-Pad1.49)") (class "Default")
      (node (ref "H1") (pin "1.49") (pinfunction "1.49_1.49") (pintype "bidirectional"))
    )
    (net (code "112") (name "unconnected-(H1-Pad1.50)") (class "Default")
      (node (ref "H1") (pin "1.50") (pinfunction "1.50_1.50") (pintype "bidirectional"))
    )
    (net (code "113") (name "unconnected-(H1-Pad1.51)") (class "Default")
      (node (ref "H1") (pin "1.51") (pinfunction "1.51_1.51") (pintype "bidirectional"))
    )
    (net (code "114") (name "unconnected-(H1-Pad1.52)") (class "Default")
      (node (ref "H1") (pin "1.52") (pinfunction "1.52_1.52") (pintype "bidirectional"))
    )
    (net (code "115") (name "unconnected-(H1-Pad2.1)") (class "Default")
      (node (ref "H1") (pin "2.1") (pinfunction "2.1_2.1") (pintype "bidirectional"))
    )
    (net (code "116") (name "unconnected-(H1-Pad2.2)") (class "Default")
      (node (ref "H1") (pin "2.2") (pinfunction "2.2_2.2") (pintype "bidirectional"))
    )
    (net (code "117") (name "unconnected-(H1-Pad2.3)") (class "Default")
      (node (ref "H1") (pin "2.3") (pinfunction "2.3_2.3") (pintype "bidirectional"))
    )
    (net (code "118") (name "unconnected-(H1-Pad2.4)") (class "Default")
      (node (ref "H1") (pin "2.4") (pinfunction "2.4_2.4") (pintype "bidirectional"))
    )
    (net (code "119") (name "unconnected-(H1-Pad2.5)") (class "Default")
      (node (ref "H1") (pin "2.5") (pinfunction "2.5_2.5") (pintype "bidirectional"))
    )
    (net (code "120") (name "unconnected-(H1-Pad2.6)") (class "Default")
      (node (ref "H1") (pin "2.6") (pinfunction "2.6_2.6") (pintype "bidirectional"))
    )
    (net (code "121") (name "unconnected-(H1-Pad2.8)") (class "Default")
      (node (ref "H1") (pin "2.8") (pinfunction "2.8_2.8") (pintype "bidirectional"))
    )
    (net (code "122") (name "unconnected-(H1-Pad2.9)") (class "Default")
      (node (ref "H1") (pin "2.9") (pinfunction "2.9_2.9") (pintype "bidirectional"))
    )
    (net (code "123") (name "unconnected-(H1-Pad2.10)") (class "Default")
      (node (ref "H1") (pin "2.10") (pinfunction "2.10_2.10") (pintype "bidirectional"))
    )
    (net (code "124") (name "unconnected-(H1-Pad2.11)") (class "Default")
      (node (ref "H1") (pin "2.11") (pinfunction "2.11_2.11") (pintype "bidirectional"))
    )
    (net (code "125") (name "unconnected-(H1-Pad2.12)") (class "Default")
      (node (ref "H1") (pin "2.12") (pinfunction "2.12_2.12") (pintype "bidirectional"))
    )
    (net (code "126") (name "unconnected-(H1-Pad2.15)") (class "Default")
      (node (ref "H1") (pin "2.15") (pinfunction "2.15_2.15") (pintype "bidirectional"))
    )
    (net (code "127") (name "unconnected-(H1-Pad2.16)") (class "Default")
      (node (ref "H1") (pin "2.16") (pinfunction "2.16_2.16") (pintype "bidirectional"))
    )
    (net (code "128") (name "unconnected-(H1-Pad2.18)") (class "Default")
      (node (ref "H1") (pin "2.18") (pinfunction "2.18_2.18") (pintype "bidirectional"))
    )
    (net (code "129") (name "unconnected-(H1-Pad2.19)") (class "Default")
      (node (ref "H1") (pin "2.19") (pinfunction "2.19_2.19") (pintype "bidirectional"))
    )
    (net (code "130") (name "unconnected-(H1-Pad2.20)") (class "Default")
      (node (ref "H1") (pin "2.20") (pinfunction "2.20_2.20") (pintype "bidirectional"))
    )
    (net (code "131") (name "unconnected-(H1-Pad2.23)") (class "Default")
      (node (ref "H1") (pin "2.23") (pinfunction "2.23_2.23") (pintype "bidirectional"))
    )
    (net (code "132") (name "unconnected-(H1-Pad2.24)") (class "Default")
      (node (ref "H1") (pin "2.24") (pinfunction "2.24_2.24") (pintype "bidirectional"))
    )
    (net (code "133") (name "unconnected-(H1-Pad2.31)") (class "Default")
      (node (ref "H1") (pin "2.31") (pinfunction "2.31_2.31") (pintype "bidirectional"))
    )
    (net (code "134") (name "unconnected-(H1-Pad2.33)") (class "Default")
      (node (ref "H1") (pin "2.33") (pinfunction "2.33_2.33") (pintype "bidirectional"))
    )
    (net (code "135") (name "unconnected-(H1-Pad2.34)") (class "Default")
      (node (ref "H1") (pin "2.34") (pinfunction "2.34_2.34") (pintype "bidirectional"))
    )
    (net (code "136") (name "unconnected-(H1-Pad2.35)") (class "Default")
      (node (ref "H1") (pin "2.35") (pinfunction "2.35_2.35") (pintype "bidirectional"))
    )
    (net (code "137") (name "unconnected-(H1-Pad2.36)") (class "Default")
      (node (ref "H1") (pin "2.36") (pinfunction "2.36_2.36") (pintype "bidirectional"))
    )
    (net (code "138") (name "unconnected-(H1-Pad2.37)") (class "Default")
      (node (ref "H1") (pin "2.37") (pinfunction "2.37_2.37") (pintype "bidirectional"))
    )
    (net (code "139") (name "unconnected-(H1-Pad2.38)") (class "Default")
      (node (ref "H1") (pin "2.38") (pinfunction "2.38_2.38") (pintype "bidirectional"))
    )
    (net (code "140") (name "unconnected-(H1-Pad2.39)") (class "Default")
      (node (ref "H1") (pin "2.39") (pinfunction "2.39_2.39") (pintype "bidirectional"))
    )
    (net (code "141") (name "unconnected-(H1-Pad2.40)") (class "Default")
      (node (ref "H1") (pin "2.40") (pinfunction "2.40_2.40") (pintype "bidirectional"))
    )
    (net (code "142") (name "unconnected-(H1-Pad2.41)") (class "Default")
      (node (ref "H1") (pin "2.41") (pinfunction "2.41_2.41") (pintype "bidirectional"))
    )
    (net (code "143") (name "unconnected-(H1-Pad2.42)") (class "Default")
      (node (ref "H1") (pin "2.42") (pinfunction "2.42_2.42") (pintype "bidirectional"))
    )
    (net (code "144") (name "unconnected-(H1-Pad2.43)") (class "Default")
      (node (ref "H1") (pin "2.43") (pinfunction "2.43_2.43") (pintype "bidirectional"))
    )
    (net (code "145") (name "unconnected-(H1-Pad2.44)") (class "Default")
      (node (ref "H1") (pin "2.44") (pinfunction "2.44_2.44") (pintype "bidirectional"))
    )
    (net (code "146") (name "unconnected-(H1-Pad2.45)") (class "Default")
      (node (ref "H1") (pin "2.45") (pinfunction "2.45_2.45") (pintype "bidirectional"))
    )
    (net (code "147") (name "unconnected-(H1-Pad2.46)") (class "Default")
      (node (ref "H1") (pin "2.46") (pinfunction "2.46_2.46") (pintype "bidirectional"))
    )
    (net (code "148") (name "unconnected-(H1-Pad2.49)") (class "Default")
      (node (ref "H1") (pin "2.49") (pinfunction "2.49_2.49") (pintype "bidirectional"))
    )
    (net (code "149") (name "unconnected-(H1-Pad2.50)") (class "Default")
      (node (ref "H1") (pin "2.50") (pinfunction "2.50_2.50") (pintype "bidirectional"))
    )
    (net (code "150") (name "unconnected-(H1-Pad2.51)") (class "Default")
      (node (ref "H1") (pin "2.51") (pinfunction "2.51_2.51") (pintype "bidirectional"))
    )
    (net (code "151") (name "unconnected-(H1-Pad2.52)") (class "Default")
      (node (ref "H1") (pin "2.52") (pinfunction "2.52_2.52") (pintype "bidirectional"))
    )
    (net (code "152") (name "unconnected-(H1-PadP$1)") (class "Default")
      (node (ref "H1") (pin "P$1") (pinfunction "P$1_P$1") (pintype "bidirectional"))
    )
    (net (code "153") (name "unconnected-(H1-PadP$2)") (class "Default")
      (node (ref "H1") (pin "P$2") (pinfunction "P$2_P$2") (pintype "bidirectional"))
    )
    (net (code "154") (name "unconnected-(H1-PadP$3)") (class "Default")
      (node (ref "H1") (pin "P$3") (pinfunction "P$3_P$3") (pintype "bidirectional"))
    )
    (net (code "155") (name "unconnected-(U$1-Pad9-OUT1C)") (class "Default")
      (node (ref "U$1") (pin "9-OUT1C") (pinfunction "9-OUT1C_9-OUT1C") (pintype "bidirectional"))
    )
    (net (code "156") (name "unconnected-(U$1-Pad30-CRX3)") (class "Default")
      (node (ref "U$1") (pin "30-CRX3") (pinfunction "30-CRX3_30-CRX3") (pintype "bidirectional"))
    )
    (net (code "157") (name "unconnected-(U$1-Pad31-CTX3)") (class "Default")
      (node (ref "U$1") (pin "31-CTX3") (pinfunction "31-CTX3_31-CTX3") (pintype "bidirectional"))
    )
    (net (code "158") (name "unconnected-(U$1-Pad32-OUT1B)") (class "Default")
      (node (ref "U$1") (pin "32-OUT1B") (pinfunction "32-OUT1B_32-OUT1B") (pintype "bidirectional"))
    )
    (net (code "159") (name "unconnected-(U$1-Pad37-PWM)") (class "Default")
      (node (ref "U$1") (pin "37-PWM") (pinfunction "37-PWM_37-PWM") (pintype "bidirectional"))
    )
    (net (code "160") (name "unconnected-(U$1-Pad40-A16{slash}CS1)") (class "Default")
      (node (ref "U$1") (pin "40-A16/CS1") (pinfunction "40-A16/CS1_40-A16/CS1") (pintype "bidirectional"))
    )
    (net (code "161") (name "unconnected-(U$1-PadON{slash}OFF)") (class "Default")
      (node (ref "U$1") (pin "ON/OFF") (pinfunction "ON/OFF_ON/OFF") (pintype "bidirectional"))
    )
    (net (code "162") (name "unconnected-(U1-NC-Pad7)") (class "Default")
      (node (ref "U1") (pin "7") (pinfunction "NC_7") (pintype "no_connect"))
    )
    (net (code "163") (name "unconnected-(U1-NC_2-Pad2)") (class "Default")
      (node (ref "U1") (pin "2") (pinfunction "NC_2_2") (pintype "no_connect"))
    )
    (net (code "164") (name "unconnected-(U1-NC_3-Pad3)") (class "Default")
      (node (ref "U1") (pin "3") (pinfunction "NC_3_3") (pintype "no_connect"))
    )
    (net (code "165") (name "unconnected-(U1-NC_4-Pad6)") (class "Default")
      (node (ref "U1") (pin "6") (pinfunction "NC_4_6") (pintype "no_connect"))
    )
    (net (code "166") (name "unconnected-(U3-DIO1-Pad11)") (class "Default")
      (node (ref "U3") (pin "11") (pinfunction "DIO1_11") (pintype "bidirectional"))
    )
    (net (code "167") (name "unconnected-(U3-DIO2-Pad12)") (class "Default")
      (node (ref "U3") (pin "12") (pinfunction "DIO2_12") (pintype "bidirectional"))
    )
    (net (code "168") (name "unconnected-(U3-DIO3-Pad13)") (class "Default")
      (node (ref "U3") (pin "13") (pinfunction "DIO3_13") (pintype "bidirectional"))
    )
    (net (code "169") (name "unconnected-(U3-DIO4-Pad14)") (class "Default")
      (node (ref "U3") (pin "14") (pinfunction "DIO4_14") (pintype "bidirectional"))
    )
    (net (code "170") (name "unconnected-(U3-DIO5-Pad15)") (class "Default")
      (node (ref "U3") (pin "15") (pinfunction "DIO5_15") (pintype "bidirectional"))
    )
    (net (code "171") (name "unconnected-(U3-NC-Pad1)") (class "Default")
      (node (ref "U3") (pin "1") (pinfunction "NC_1") (pintype "bidirectional"))
    )
    (net (code "172") (name "unconnected-(U5-Pad1)") (class "Default")
      (node (ref "U5") (pin "1") (pinfunction "1_1") (pintype "passive"))
    )
    (net (code "173") (name "unconnected-(U6-P$3-Pad3)") (class "Default")
      (node (ref "U6") (pin "3") (pinfunction "P$3_3") (pintype "bidirectional"))
    )
    (net (code "174") (name "unconnected-(U6-P$4-Pad4)") (class "Default")
      (node (ref "U6") (pin "4") (pinfunction "P$4_4") (pintype "bidirectional"))
    )
    (net (code "175") (name "unconnected-(U6-P$5-Pad5)") (class "Default")
      (node (ref "U6") (pin "5") (pinfunction "P$5_5") (pintype "bidirectional"))
    )
    (net (code "176") (name "unconnected-(U6-P$6-Pad6)") (class "Default")
      (node (ref "U6") (pin "6") (pinfunction "P$6_6") (pintype "bidirectional"))
    )
    (net (code "177") (name "unconnected-(U6-P$8-Pad8)") (class "Default")
      (node (ref "U6") (pin "8") (pinfunction "P$8_8") (pintype "bidirectional"))
    )
    (net (code "178") (name "unconnected-(U6-P$12-Pad12)") (class "Default")
      (node (ref "U6") (pin "12") (pinfunction "P$12_12") (pintype "bidirectional"))
    )
    (net (code "179") (name "unconnected-(U6-P$13-Pad13)") (class "Default")
      (node (ref "U6") (pin "13") (pinfunction "P$13_13") (pintype "bidirectional"))
    )
    (net (code "180") (name "unconnected-(U6-P$14-Pad14)") (class "Default")
      (node (ref "U6") (pin "14") (pinfunction "P$14_14") (pintype "bidirectional"))
    )
    (net (code "181") (name "unconnected-(U6-P$16-Pad16)") (class "Default")
      (node (ref "U6") (pin "16") (pinfunction "P$16_16") (pintype "bidirectional"))
    )
    (net (code "182") (name "unconnected-(U6-P$17-Pad17)") (class "Default")
      (node (ref "U6") (pin "17") (pinfunction "P$17_17") (pintype "bidirectional"))
    )
    (net (code "183") (name "unconnected-(U6-P$20-Pad20)") (class "Default")
      (node (ref "U6") (pin "20") (pinfunction "P$20_20") (pintype "bidirectional"))
    )
    (net (code "184") (name "unconnected-(U6-P$23-Pad23)") (class "Default")
      (node (ref "U6") (pin "23") (pinfunction "P$23_23") (pintype "bidirectional"))
    )
    (net (code "185") (name "unconnected-(U6-P$26-Pad26)") (class "Default")
      (node (ref "U6") (pin "26") (pinfunction "P$26_26") (pintype "bidirectional"))
    )
    (net (code "186") (name "unconnected-(U6-P$30-Pad30)") (class "Default")
      (node (ref "U6") (pin "30") (pinfunction "P$30_30") (pintype "bidirectional"))
    )
    (net (code "187") (name "unconnected-(U6-P$34-Pad34)") (class "Default")
      (node (ref "U6") (pin "34") (pinfunction "P$34_34") (pintype "bidirectional"))
    )
    (net (code "188") (name "unconnected-(U6-P$35-Pad35)") (class "Default")
      (node (ref "U6") (pin "35") (pinfunction "P$35_35") (pintype "bidirectional"))
    )
    (net (code "189") (name "unconnected-(U6-P$36-Pad36)") (class "Default")
      (node (ref "U6") (pin "36") (pinfunction "P$36_36") (pintype "bidirectional"))
    )
    (net (code "190") (name "unconnected-(U6-P$37-Pad37)") (class "Default")
      (node (ref "U6") (pin "37") (pinfunction "P$37_37") (pintype "bidirectional"))
    )
    (net (code "191") (name "unconnected-(U6-P$38-Pad38)") (class "Default")
      (node (ref "U6") (pin "38") (pinfunction "P$38_38") (pintype "bidirectional"))
    )
    (net (code "192") (name "unconnected-(U6-P$39-Pad39)") (class "Default")
      (node (ref "U6") (pin "39") (pinfunction "P$39_39") (pintype "bidirectional"))
    )
    (net (code "193") (name "unconnected-(U6-P$40-Pad40)") (class "Default")
      (node (ref "U6") (pin "40") (pinfunction "P$40_40") (pintype "bidirectional"))
    )
    (net (code "194") (name "unconnected-(U6-P$41-Pad41)") (class "Default")
      (node (ref "U6") (pin "41") (pinfunction "P$41_41") (pintype "bidirectional"))
    )
    (net (code "195") (name "unconnected-(U6-P$43-Pad43)") (class "Default")
      (node (ref "U6") (pin "43") (pinfunction "P$43_43") (pintype "bidirectional"))
    )
    (net (code "196") (name "unconnected-(U6-P$45-Pad45)") (class "Default")
      (node (ref "U6") (pin "45") (pinfunction "P$45_45") (pintype "bidirectional"))
    )
    (net (code "197") (name "unconnected-(U6-P$46-Pad46)") (class "Default")
      (node (ref "U6") (pin "46") (pinfunction "P$46_46") (pintype "bidirectional"))
    )
    (net (code "198") (name "unconnected-(U6-P$47-Pad47)") (class "Default")
      (node (ref "U6") (pin "47") (pinfunction "P$47_47") (pintype "bidirectional"))
    )
    (net (code "199") (name "unconnected-(U6-P$48-Pad48)") (class "Default")
      (node (ref "U6") (pin "48") (pinfunction "P$48_48") (pintype "bidirectional"))
    )
    (net (code "200") (name "unconnected-(U6-P$49-Pad49)") (class "Default")
      (node (ref "U6") (pin "49") (pinfunction "P$49_49") (pintype "bidirectional"))
    )
    (net (code "201") (name "unconnected-(U6-P$50-Pad50)") (class "Default")
      (node (ref "U6") (pin "50") (pinfunction "P$50_50") (pintype "bidirectional"))
    )
    (net (code "202") (name "unconnected-(U6-P$51-Pad51)") (class "Default")
      (node (ref "U6") (pin "51") (pinfunction "P$51_51") (pintype "bidirectional"))
    )
    (net (code "203") (name "unconnected-(U6-P$52-Pad52)") (class "Default")
      (node (ref "U6") (pin "52") (pinfunction "P$52_52") (pintype "bidirectional"))
    )
    (net (code "204") (name "unconnected-(U6-P$53-Pad53)") (class "Default")
      (node (ref "U6") (pin "53") (pinfunction "P$53_53") (pintype "bidirectional"))
    )
    (net (code "205") (name "unconnected-(U6-P$54-Pad54)") (class "Default")
      (node (ref "U6") (pin "54") (pinfunction "P$54_54") (pintype "bidirectional"))
    )
    (net (code "206") (name "unconnected-(U6-P$55-Pad55)") (class "Default")
      (node (ref "U6") (pin "55") (pinfunction "P$55_55") (pintype "bidirectional"))
    )
    (net (code "207") (name "unconnected-(U6-P$56-Pad56)") (class "Default")
      (node (ref "U6") (pin "56") (pinfunction "P$56_56") (pintype "bidirectional"))
    )
    (net (code "208") (name "unconnected-(U6-P$57-Pad57)") (class "Default")
      (node (ref "U6") (pin "57") (pinfunction "P$57_57") (pintype "bidirectional"))
    )
    (net (code "209") (name "unconnected-(U6-P$59-Pad59)") (class "Default")
      (node (ref "U6") (pin "59") (pinfunction "P$59_59") (pintype "bidirectional"))
    )
    (net (code "210") (name "unconnected-(U6-P$60-Pad60)") (class "Default")
      (node (ref "U6") (pin "60") (pinfunction "P$60_60") (pintype "bidirectional"))
    )
    (net (code "211") (name "unconnected-(U6-P$61-Pad61)") (class "Default")
      (node (ref "U6") (pin "61") (pinfunction "P$61_61") (pintype "bidirectional"))
    )
    (net (code "212") (name "unconnected-(U6-P$62-Pad62)") (class "Default")
      (node (ref "U6") (pin "62") (pinfunction "P$62_62") (pintype "bidirectional"))
    )
    (net (code "213") (name "unconnected-(U6-P$63-Pad63)") (class "Default")
      (node (ref "U6") (pin "63") (pinfunction "P$63_63") (pintype "bidirectional"))
    )
    (net (code "214") (name "unconnected-(U6-P$65-Pad65)") (class "Default")
      (node (ref "U6") (pin "65") (pinfunction "P$65_65") (pintype "bidirectional"))
    )
    (net (code "215") (name "unconnected-(U6-P$66-Pad66)") (class "Default")
      (node (ref "U6") (pin "66") (pinfunction "P$66_66") (pintype "bidirectional"))
    )
    (net (code "216") (name "unconnected-(U6-P$67-Pad67)") (class "Default")
      (node (ref "U6") (pin "67") (pinfunction "P$67_67") (pintype "bidirectional"))
    )
    (net (code "217") (name "unconnected-(U6-P$68-Pad68)") (class "Default")
      (node (ref "U6") (pin "68") (pinfunction "P$68_68") (pintype "bidirectional"))
    )
    (net (code "218") (name "unconnected-(U6-P$69-Pad69)") (class "Default")
      (node (ref "U6") (pin "69") (pinfunction "P$69_69") (pintype "bidirectional"))
    )
    (net (code "219") (name "unconnected-(X1-P$1-Pad1)") (class "Default")
      (node (ref "X1") (pin "1") (pinfunction "P$1_1") (pintype "bidirectional"))
    )
    (net (code "220") (name "unconnected-(X1-P$4-Pad4)") (class "Default")
      (node (ref "X1") (pin "4") (pinfunction "P$4_4") (pintype "bidirectional"))
    )
    (net (code "221") (name "unconnected-(X1-P$6-Pad6)") (class "Default")
      (node (ref "X1") (pin "6") (pinfunction "P$6_6") (pintype "bidirectional"))
    )
    (net (code "222") (name "unconnected-(X1-P$7-Pad7)") (class "Default")
      (node (ref "X1") (pin "7") (pinfunction "P$7_7") (pintype "bidirectional"))
    )
    (net (code "223") (name "unconnected-(X1-P$8-Pad8)") (class "Default")
      (node (ref "X1") (pin "8") (pinfunction "P$8_8") (pintype "bidirectional"))
    )
    (net (code "224") (name "unconnected-(X1-P$9-Pad9)") (class "Default")
      (node (ref "X1") (pin "9") (pinfunction "P$9_9") (pintype "bidirectional"))
    )
    (net (code "225") (name "unconnected-(X1-P$10-Pad10)") (class "Default")
      (node (ref "X1") (pin "10") (pinfunction "P$10_10") (pintype "bidirectional"))
    )
    (net (code "226") (name "unconnected-(X1-P$12-Pad12)") (class "Default")
      (node (ref "X1") (pin "12") (pinfunction "P$12_12") (pintype "bidirectional"))
    )
    (net (code "227") (name "unconnected-(X1-P$14-Pad14)") (class "Default")
      (node (ref "X1") (pin "14") (pinfunction "P$14_14") (pintype "bidirectional"))
    )
    (net (code "228") (name "unconnected-(X1-P$17-Pad17)") (class "Default")
      (node (ref "X1") (pin "17") (pinfunction "P$17_17") (pintype "bidirectional"))
    )
    (net (code "229") (name "unconnected-(X1-P$20-Pad20)") (class "Default")
      (node (ref "X1") (pin "20") (pinfunction "P$20_20") (pintype "bidirectional"))
    )
    (net (code "230") (name "unconnected-(X1-P$25-Pad25)") (class "Default")
      (node (ref "X1") (pin "25") (pinfunction "P$25_25") (pintype "bidirectional"))
    )
    (net (code "231") (name "unconnected-(X1-P$27-Pad27)") (class "Default")
      (node (ref "X1") (pin "27") (pinfunction "P$27_27") (pintype "bidirectional"))
    )
    (net (code "232") (name "unconnected-(X1-P$28-Pad28)") (class "Default")
      (node (ref "X1") (pin "28") (pinfunction "P$28_28") (pintype "bidirectional"))
    )
    (net (code "233") (name "unconnected-(X1-P$29-Pad29)") (class "Default")
      (node (ref "X1") (pin "29") (pinfunction "P$29_29") (pintype "bidirectional"))
    )
    (net (code "234") (name "unconnected-(X1-P$30-Pad30)") (class "Default")
      (node (ref "X1") (pin "30") (pinfunction "P$30_30") (pintype "bidirectional"))
    )
    (net (code "235") (name "unconnected-(X1-P$31-Pad31)") (class "Default")
      (node (ref "X1") (pin "31") (pinfunction "P$31_31") (pintype "bidirectional"))
    )
    (net (code "236") (name "unconnected-(X1-P$32-Pad32)") (class "Default")
      (node (ref "X1") (pin "32") (pinfunction "P$32_32") (pintype "bidirectional"))
    )
    (net (code "237") (name "unconnected-(X1-P$33-Pad33)") (class "Default")
      (node (ref "X1") (pin "33") (pinfunction "P$33_33") (pintype "bidirectional"))
    )
    (net (code "238") (name "unconnected-(X1-P$34-Pad34)") (class "Default")
      (node (ref "X1") (pin "34") (pinfunction "P$34_34") (pintype "bidirectional"))
    )
    (net (code "239") (name "unconnected-(X1-P$35-Pad35)") (class "Default")
      (node (ref "X1") (pin "35") (pinfunction "P$35_35") (pintype "bidirectional"))
    )
    (net (code "240") (name "unconnected-(X1-P$36-Pad36)") (class "Default")
      (node (ref "X1") (pin "36") (pinfunction "P$36_36") (pintype "bidirectional"))
    )
    (net (code "241") (name "unconnected-(X1-P$37-Pad37)") (class "Default")
      (node (ref "X1") (pin "37") (pinfunction "P$37_37") (pintype "bidirectional"))
    )
    (net (code "242") (name "unconnected-(X1-P$38-Pad38)") (class "Default")
      (node (ref "X1") (pin "38") (pinfunction "P$38_38") (pintype "bidirectional"))
    )
    (net (code "243") (name "unconnected-(X1-P$40-Pad40)") (class "Default")
      (node (ref "X1") (pin "40") (pinfunction "P$40_40") (pintype "bidirectional"))
    )
    (net (code "244") (name "unconnected-(X2-Pad1)") (class "Default")
      (node (ref "X2") (pin "1") (pinfunction "1_1") (pintype "passive"))
    )
    (net (code "245") (name "unconnected-(X2AA-1-Pad33)") (class "Default")
      (node (ref "X2") (pin "33") (pinfunction "1_33") (pintype "passive"))
    )
    (net (code "246") (name "unconnected-(X2AB-1-Pad34)") (class "Default")
      (node (ref "X2") (pin "34") (pinfunction "1_34") (pintype "passive"))
    )
    (net (code "247") (name "unconnected-(X2AC-1-Pad35)") (class "Default")
      (node (ref "X2") (pin "35") (pinfunction "1_35") (pintype "passive"))
    )
    (net (code "248") (name "unconnected-(X2AD-1-Pad36)") (class "Default")
      (node (ref "X2") (pin "36") (pinfunction "1_36") (pintype "passive"))
    )
    (net (code "249") (name "unconnected-(X2AE-1-Pad37)") (class "Default")
      (node (ref "X2") (pin "37") (pinfunction "1_37") (pintype "passive"))
    )
    (net (code "250") (name "unconnected-(X2AF-1-Pad38)") (class "Default")
      (node (ref "X2") (pin "38") (pinfunction "1_38") (pintype "passive"))
    )
    (net (code "251") (name "unconnected-(X2AG-1-Pad39)") (class "Default")
      (node (ref "X2") (pin "39") (pinfunction "1_39") (pintype "passive"))
    )
    (net (code "252") (name "unconnected-(X2AH-1-Pad4)") (class "Default")
      (node (ref "X2") (pin "4") (pinfunction "1_4") (pintype "passive"))
    )
    (net (code "253") (name "unconnected-(X2AI-1-Pad40)") (class "Default")
      (node (ref "X2") (pin "40") (pinfunction "1_40") (pintype "passive"))
    )
    (net (code "254") (name "unconnected-(X2AJ-1-Pad5)") (class "Default")
      (node (ref "X2") (pin "5") (pinfunction "1_5") (pintype "passive"))
    )
    (net (code "255") (name "unconnected-(X2AK-1-Pad6)") (class "Default")
      (node (ref "X2") (pin "6") (pinfunction "1_6") (pintype "passive"))
    )
    (net (code "256") (name "unconnected-(X2AL-1-Pad7)") (class "Default")
      (node (ref "X2") (pin "7") (pinfunction "1_7") (pintype "passive"))
    )
    (net (code "257") (name "unconnected-(X2AM-1-Pad8)") (class "Default")
      (node (ref "X2") (pin "8") (pinfunction "1_8") (pintype "passive"))
    )
    (net (code "258") (name "unconnected-(X2AN-1-Pad9)") (class "Default")
      (node (ref "X2") (pin "9") (pinfunction "1_9") (pintype "passive"))
    )
    (net (code "259") (name "unconnected-(X2B-1-Pad10)") (class "Default")
      (node (ref "X2") (pin "10") (pinfunction "1_10") (pintype "passive"))
    )
    (net (code "260") (name "unconnected-(X2C-1-Pad11)") (class "Default")
      (node (ref "X2") (pin "11") (pinfunction "1_11") (pintype "passive"))
    )
    (net (code "261") (name "unconnected-(X2D-1-Pad12)") (class "Default")
      (node (ref "X2") (pin "12") (pinfunction "1_12") (pintype "passive"))
    )
    (net (code "262") (name "unconnected-(X2E-1-Pad13)") (class "Default")
      (node (ref "X2") (pin "13") (pinfunction "1_13") (pintype "passive"))
    )
    (net (code "263") (name "unconnected-(X2F-1-Pad14)") (class "Default")
      (node (ref "X2") (pin "14") (pinfunction "1_14") (pintype "passive"))
    )
    (net (code "264") (name "unconnected-(X2G-1-Pad15)") (class "Default")
      (node (ref "X2") (pin "15") (pinfunction "1_15") (pintype "passive"))
    )
    (net (code "265") (name "unconnected-(X2H-1-Pad16)") (class "Default")
      (node (ref "X2") (pin "16") (pinfunction "1_16") (pintype "passive"))
    )
    (net (code "266") (name "unconnected-(X2I-1-Pad17)") (class "Default")
      (node (ref "X2") (pin "17") (pinfunction "1_17") (pintype "passive"))
    )
    (net (code "267") (name "unconnected-(X2J-1-Pad18)") (class "Default")
      (node (ref "X2") (pin "18") (pinfunction "1_18") (pintype "passive"))
    )
    (net (code "268") (name "unconnected-(X2K-1-Pad19)") (class "Default")
      (node (ref "X2") (pin "19") (pinfunction "1_19") (pintype "passive"))
    )
    (net (code "269") (name "unconnected-(X2L-1-Pad2)") (class "Default")
      (node (ref "X2") (pin "2") (pinfunction "1_2") (pintype "passive"))
    )
    (net (code "270") (name "unconnected-(X2M-1-Pad20)") (class "Default")
      (node (ref "X2") (pin "20") (pinfunction "1_20") (pintype "passive"))
    )
    (net (code "271") (name "unconnected-(X2N-1-Pad21)") (class "Default")
      (node (ref "X2") (pin "21") (pinfunction "1_21") (pintype "passive"))
    )
    (net (code "272") (name "unconnected-(X2O-1-Pad22)") (class "Default")
      (node (ref "X2") (pin "22") (pinfunction "1_22") (pintype "passive"))
    )
    (net (code "273") (name "unconnected-(X2P-1-Pad23)") (class "Default")
      (node (ref "X2") (pin "23") (pinfunction "1_23") (pintype "passive"))
    )
    (net (code "274") (name "unconnected-(X2Q-1-Pad24)") (class "Default")
      (node (ref "X2") (pin "24") (pinfunction "1_24") (pintype "passive"))
    )
    (net (code "275") (name "unconnected-(X2R-1-Pad25)") (class "Default")
      (node (ref "X2") (pin "25") (pinfunction "1_25") (pintype "passive"))
    )
    (net (code "276") (name "unconnected-(X2S-1-Pad26)") (class "Default")
      (node (ref "X2") (pin "26") (pinfunction "1_26") (pintype "passive"))
    )
    (net (code "277") (name "unconnected-(X2T-1-Pad27)") (class "Default")
      (node (ref "X2") (pin "27") (pinfunction "1_27") (pintype "passive"))
    )
    (net (code "278") (name "unconnected-(X2U-1-Pad28)") (class "Default")
      (node (ref "X2") (pin "28") (pinfunction "1_28") (pintype "passive"))
    )
    (net (code "279") (name "unconnected-(X2V-1-Pad29)") (class "Default")
      (node (ref "X2") (pin "29") (pinfunction "1_29") (pintype "passive"))
    )
    (net (code "280") (name "unconnected-(X2W-1-Pad3)") (class "Default")
      (node (ref "X2") (pin "3") (pinfunction "1_3") (pintype "passive"))
    )
    (net (code "281") (name "unconnected-(X2X-1-Pad30)") (class "Default")
      (node (ref "X2") (pin "30") (pinfunction "1_30") (pintype "passive"))
    )
    (net (code "282") (name "unconnected-(X2Y-1-Pad31)") (class "Default")
      (node (ref "X2") (pin "31") (pinfunction "1_31") (pintype "passive"))
    )
    (net (code "283") (name "unconnected-(X2Z-1-Pad32)") (class "Default")
      (node (ref "X2") (pin "32") (pinfunction "1_32") (pintype "passive"))
    )
  )
)
